# PCB_-_alu40_-_mupusb.net
KiCad netlist of a schematic drawn in EAGLE
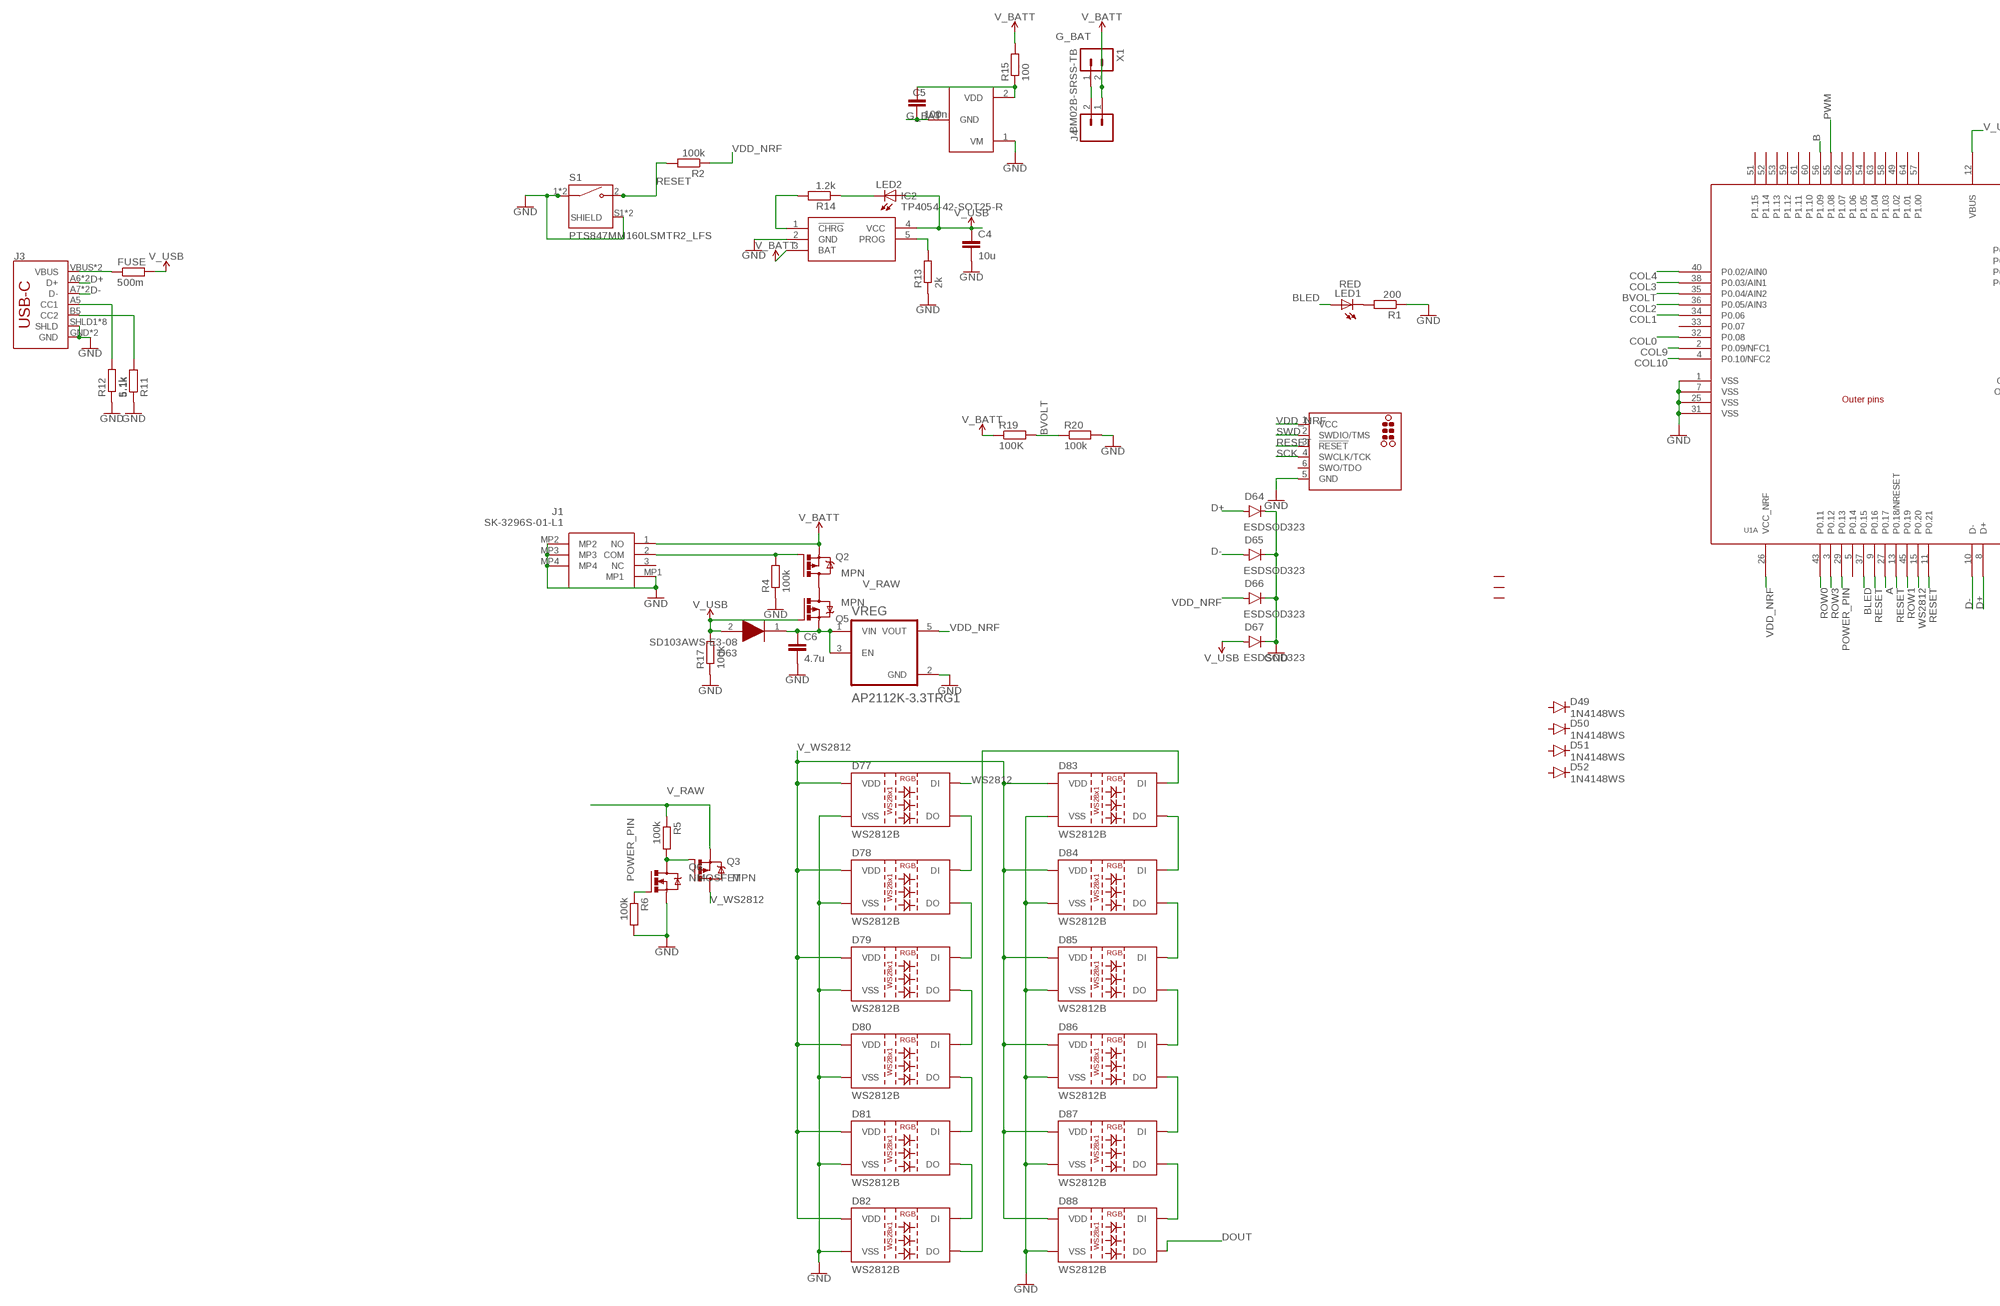
[diagram p0: schematic, sheet 1, part 1 of 2]
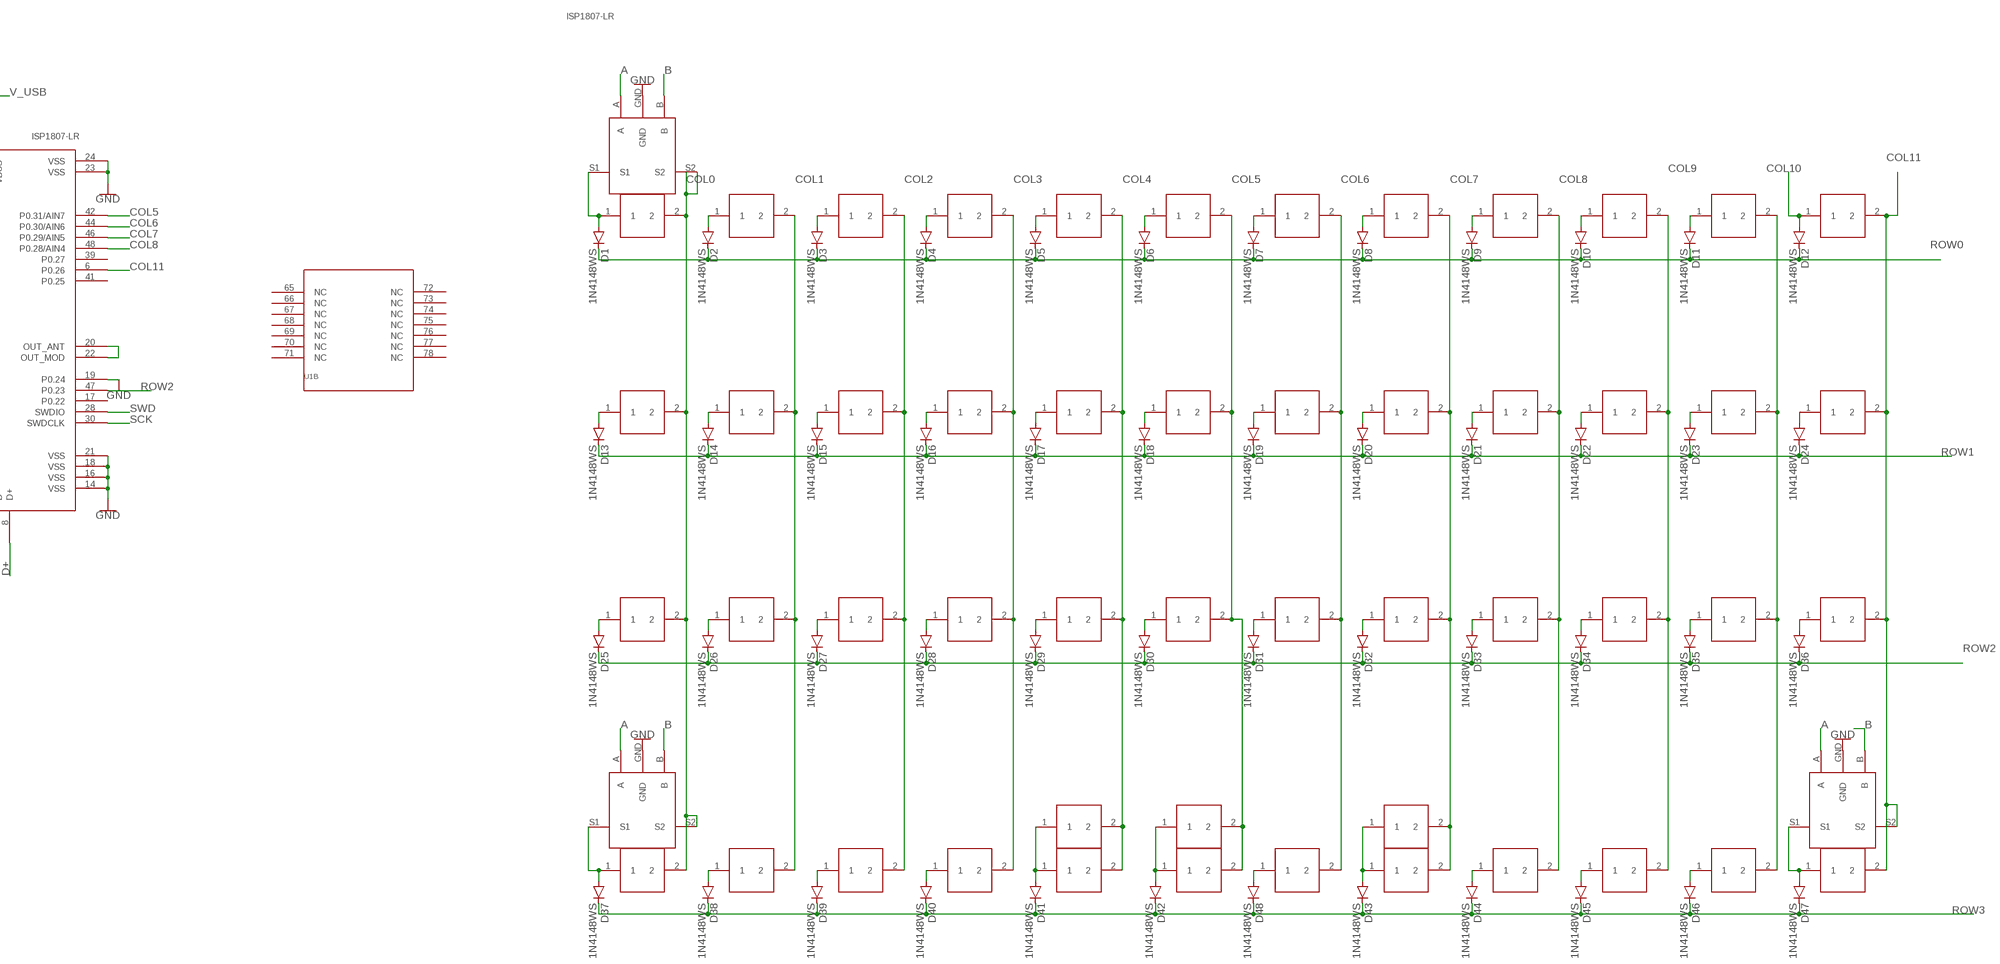
[diagram p1: schematic, sheet 1, part 2 of 2]

(export (version "E")
  (design (tool "Eeschema 10.0.6"))
  (components
    (comp (ref "11")
      (value "CHERRY")
      (footprint "eagle-import:CHERRY")
      (libsource (lib "eagle-import") (part "CHERRY"))
    )
    (comp (ref "11ENC")
      (value "ENCODERHOLE")
      (footprint "eagle-import:ENCODER")
      (libsource (lib "eagle-import") (part "ENCODERHOLE"))
    )
    (comp (ref "12")
      (value "CHERRY")
      (footprint "eagle-import:CHERRY")
      (libsource (lib "eagle-import") (part "CHERRY"))
    )
    (comp (ref "13")
      (value "CHERRY")
      (footprint "eagle-import:CHERRY")
      (libsource (lib "eagle-import") (part "CHERRY"))
    )
    (comp (ref "14")
      (value "CHERRY")
      (footprint "eagle-import:CHERRY")
      (libsource (lib "eagle-import") (part "CHERRY"))
    )
    (comp (ref "15")
      (value "CHERRY")
      (footprint "eagle-import:CHERRY")
      (libsource (lib "eagle-import") (part "CHERRY"))
    )
    (comp (ref "16")
      (value "CHERRY")
      (footprint "eagle-import:CHERRY")
      (libsource (lib "eagle-import") (part "CHERRY"))
    )
    (comp (ref "17")
      (value "CHERRY")
      (footprint "eagle-import:CHERRY")
      (libsource (lib "eagle-import") (part "CHERRY"))
    )
    (comp (ref "18")
      (value "CHERRY")
      (footprint "eagle-import:CHERRY")
      (libsource (lib "eagle-import") (part "CHERRY"))
    )
    (comp (ref "19")
      (value "CHERRY")
      (footprint "eagle-import:CHERRY")
      (libsource (lib "eagle-import") (part "CHERRY"))
    )
    (comp (ref "21")
      (value "CHERRY")
      (footprint "eagle-import:CHERRY")
      (libsource (lib "eagle-import") (part "CHERRY"))
    )
    (comp (ref "22")
      (value "CHERRY")
      (footprint "eagle-import:CHERRY")
      (libsource (lib "eagle-import") (part "CHERRY"))
    )
    (comp (ref "23")
      (value "CHERRY")
      (footprint "eagle-import:CHERRY")
      (libsource (lib "eagle-import") (part "CHERRY"))
    )
    (comp (ref "24")
      (value "CHERRY")
      (footprint "eagle-import:CHERRY")
      (libsource (lib "eagle-import") (part "CHERRY"))
    )
    (comp (ref "25")
      (value "CHERRY")
      (footprint "eagle-import:CHERRY")
      (libsource (lib "eagle-import") (part "CHERRY"))
    )
    (comp (ref "26")
      (value "CHERRY")
      (footprint "eagle-import:CHERRY")
      (libsource (lib "eagle-import") (part "CHERRY"))
    )
    (comp (ref "27")
      (value "CHERRY")
      (footprint "eagle-import:CHERRY")
      (libsource (lib "eagle-import") (part "CHERRY"))
    )
    (comp (ref "28")
      (value "CHERRY")
      (footprint "eagle-import:CHERRY")
      (libsource (lib "eagle-import") (part "CHERRY"))
    )
    (comp (ref "29")
      (value "CHERRY")
      (footprint "eagle-import:CHERRY")
      (libsource (lib "eagle-import") (part "CHERRY"))
    )
    (comp (ref "31")
      (value "CHERRY")
      (footprint "eagle-import:CHERRY")
      (libsource (lib "eagle-import") (part "CHERRY"))
    )
    (comp (ref "32")
      (value "CHERRY")
      (footprint "eagle-import:CHERRY")
      (libsource (lib "eagle-import") (part "CHERRY"))
    )
    (comp (ref "33")
      (value "CHERRY")
      (footprint "eagle-import:CHERRY")
      (libsource (lib "eagle-import") (part "CHERRY"))
    )
    (comp (ref "34")
      (value "CHERRY")
      (footprint "eagle-import:CHERRY")
      (libsource (lib "eagle-import") (part "CHERRY"))
    )
    (comp (ref "35")
      (value "CHERRY")
      (footprint "eagle-import:CHERRY")
      (libsource (lib "eagle-import") (part "CHERRY"))
    )
    (comp (ref "36")
      (value "CHERRY")
      (footprint "eagle-import:CHERRY")
      (libsource (lib "eagle-import") (part "CHERRY"))
    )
    (comp (ref "37")
      (value "CHERRY")
      (footprint "eagle-import:CHERRY")
      (libsource (lib "eagle-import") (part "CHERRY"))
    )
    (comp (ref "38")
      (value "CHERRY")
      (footprint "eagle-import:CHERRY")
      (libsource (lib "eagle-import") (part "CHERRY"))
    )
    (comp (ref "39")
      (value "CHERRY")
      (footprint "eagle-import:CHERRY")
      (libsource (lib "eagle-import") (part "CHERRY"))
    )
    (comp (ref "41")
      (value "CHERRY")
      (footprint "eagle-import:CHERRY")
      (libsource (lib "eagle-import") (part "CHERRY"))
    )
    (comp (ref "41ENC\\")
      (value "ENCODERHOLE")
      (footprint "eagle-import:ENCODER")
      (libsource (lib "eagle-import") (part "ENCODERHOLE"))
    )
    (comp (ref "42")
      (value "CHERRY")
      (footprint "eagle-import:CHERRY")
      (libsource (lib "eagle-import") (part "CHERRY"))
    )
    (comp (ref "43")
      (value "CHERRY")
      (footprint "eagle-import:CHERRY")
      (libsource (lib "eagle-import") (part "CHERRY"))
    )
    (comp (ref "44")
      (value "CHERRY")
      (footprint "eagle-import:CHERRY")
      (libsource (lib "eagle-import") (part "CHERRY"))
    )
    (comp (ref "45")
      (value "CHERRY")
      (footprint "eagle-import:CHERRY")
      (libsource (lib "eagle-import") (part "CHERRY"))
    )
    (comp (ref "45-2")
      (value "CHERRY")
      (footprint "eagle-import:CHERRY")
      (libsource (lib "eagle-import") (part "CHERRY"))
    )
    (comp (ref "46")
      (value "CHERRY")
      (footprint "eagle-import:CHERRY")
      (libsource (lib "eagle-import") (part "CHERRY"))
    )
    (comp (ref "46-2")
      (value "CHERRY")
      (footprint "eagle-import:CHERRY")
      (libsource (lib "eagle-import") (part "CHERRY"))
    )
    (comp (ref "47")
      (value "CHERRY")
      (footprint "eagle-import:CHERRY")
      (libsource (lib "eagle-import") (part "CHERRY"))
    )
    (comp (ref "48")
      (value "CHERRY")
      (footprint "eagle-import:CHERRY")
      (libsource (lib "eagle-import") (part "CHERRY"))
    )
    (comp (ref "48-2")
      (value "CHERRY")
      (footprint "eagle-import:CHERRY")
      (libsource (lib "eagle-import") (part "CHERRY"))
    )
    (comp (ref "49")
      (value "CHERRY")
      (footprint "eagle-import:CHERRY")
      (libsource (lib "eagle-import") (part "CHERRY"))
    )
    (comp (ref "110")
      (value "CHERRY")
      (footprint "eagle-import:CHERRY")
      (libsource (lib "eagle-import") (part "CHERRY"))
    )
    (comp (ref "111")
      (value "CHERRY")
      (footprint "eagle-import:CHERRY")
      (libsource (lib "eagle-import") (part "CHERRY"))
    )
    (comp (ref "112")
      (value "CHERRY")
      (footprint "eagle-import:CHERRY")
      (libsource (lib "eagle-import") (part "CHERRY"))
    )
    (comp (ref "210")
      (value "CHERRY")
      (footprint "eagle-import:CHERRY")
      (libsource (lib "eagle-import") (part "CHERRY"))
    )
    (comp (ref "211")
      (value "CHERRY")
      (footprint "eagle-import:CHERRY")
      (libsource (lib "eagle-import") (part "CHERRY"))
    )
    (comp (ref "212")
      (value "CHERRY")
      (footprint "eagle-import:CHERRY")
      (libsource (lib "eagle-import") (part "CHERRY"))
    )
    (comp (ref "310")
      (value "CHERRY")
      (footprint "eagle-import:CHERRY")
      (libsource (lib "eagle-import") (part "CHERRY"))
    )
    (comp (ref "311")
      (value "CHERRY")
      (footprint "eagle-import:CHERRY")
      (libsource (lib "eagle-import") (part "CHERRY"))
    )
    (comp (ref "312")
      (value "CHERRY")
      (footprint "eagle-import:CHERRY")
      (libsource (lib "eagle-import") (part "CHERRY"))
    )
    (comp (ref "410")
      (value "CHERRY")
      (footprint "eagle-import:CHERRY")
      (libsource (lib "eagle-import") (part "CHERRY"))
    )
    (comp (ref "411")
      (value "CHERRY")
      (footprint "eagle-import:CHERRY")
      (libsource (lib "eagle-import") (part "CHERRY"))
    )
    (comp (ref "412")
      (value "CHERRY")
      (footprint "eagle-import:CHERRY")
      (libsource (lib "eagle-import") (part "CHERRY"))
    )
    (comp (ref "412ENC")
      (value "ENCODERHOLE")
      (footprint "eagle-import:ENCODER")
      (libsource (lib "eagle-import") (part "ENCODERHOLE"))
    )
    (comp (ref "C4")
      (value "10u")
      (footprint "eagle-import:C0603")
      (libsource (lib "eagle-import") (part "resistor_348_C-EUC0603"))
    )
    (comp (ref "C5")
      (value "100n")
      (footprint "eagle-import:C0603")
      (libsource (lib "eagle-import") (part "resistor_348_C-EUC0603"))
    )
    (comp (ref "C6")
      (value "4.7u")
      (footprint "eagle-import:C0603")
      (libsource (lib "eagle-import") (part "C-EUC0603"))
    )
    (comp (ref "D1")
      (value "1N4148WS")
      (footprint "eagle-import:SOD-323")
      (fields
        (field (name "DIGIKEY_PART_NUMBER") "1N4148WSFSTR-ND")
        (field (name "MANUFACTURER") "Diodes Incorporated")
        (field (name "CREATED_BY") "PCBLayout.com")
      )
      (libsource (lib "eagle-import") (part "1N4148WS"))
    )
    (comp (ref "D2")
      (value "1N4148WS")
      (footprint "eagle-import:SOD-323")
      (fields
        (field (name "DIGIKEY_PART_NUMBER") "1N4148WSFSTR-ND")
        (field (name "MANUFACTURER") "Diodes Incorporated")
        (field (name "CREATED_BY") "PCBLayout.com")
      )
      (libsource (lib "eagle-import") (part "1N4148WS"))
    )
    (comp (ref "D3")
      (value "1N4148WS")
      (footprint "eagle-import:SOD-323")
      (fields
        (field (name "DIGIKEY_PART_NUMBER") "1N4148WSFSTR-ND")
        (field (name "MANUFACTURER") "Diodes Incorporated")
        (field (name "CREATED_BY") "PCBLayout.com")
      )
      (libsource (lib "eagle-import") (part "1N4148WS"))
    )
    (comp (ref "D4")
      (value "1N4148WS")
      (footprint "eagle-import:SOD-323")
      (fields
        (field (name "DIGIKEY_PART_NUMBER") "1N4148WSFSTR-ND")
        (field (name "MANUFACTURER") "Diodes Incorporated")
        (field (name "CREATED_BY") "PCBLayout.com")
      )
      (libsource (lib "eagle-import") (part "1N4148WS"))
    )
    (comp (ref "D5")
      (value "1N4148WS")
      (footprint "eagle-import:SOD-323")
      (fields
        (field (name "DIGIKEY_PART_NUMBER") "1N4148WSFSTR-ND")
        (field (name "MANUFACTURER") "Diodes Incorporated")
        (field (name "CREATED_BY") "PCBLayout.com")
      )
      (libsource (lib "eagle-import") (part "1N4148WS"))
    )
    (comp (ref "D6")
      (value "1N4148WS")
      (footprint "eagle-import:SOD-323")
      (fields
        (field (name "DIGIKEY_PART_NUMBER") "1N4148WSFSTR-ND")
        (field (name "MANUFACTURER") "Diodes Incorporated")
        (field (name "CREATED_BY") "PCBLayout.com")
      )
      (libsource (lib "eagle-import") (part "1N4148WS"))
    )
    (comp (ref "D7")
      (value "1N4148WS")
      (footprint "eagle-import:SOD-323")
      (fields
        (field (name "DIGIKEY_PART_NUMBER") "1N4148WSFSTR-ND")
        (field (name "MANUFACTURER") "Diodes Incorporated")
        (field (name "CREATED_BY") "PCBLayout.com")
      )
      (libsource (lib "eagle-import") (part "1N4148WS"))
    )
    (comp (ref "D8")
      (value "1N4148WS")
      (footprint "eagle-import:SOD-323")
      (fields
        (field (name "DIGIKEY_PART_NUMBER") "1N4148WSFSTR-ND")
        (field (name "MANUFACTURER") "Diodes Incorporated")
        (field (name "CREATED_BY") "PCBLayout.com")
      )
      (libsource (lib "eagle-import") (part "1N4148WS"))
    )
    (comp (ref "D9")
      (value "1N4148WS")
      (footprint "eagle-import:SOD-323")
      (fields
        (field (name "DIGIKEY_PART_NUMBER") "1N4148WSFSTR-ND")
        (field (name "MANUFACTURER") "Diodes Incorporated")
        (field (name "CREATED_BY") "PCBLayout.com")
      )
      (libsource (lib "eagle-import") (part "1N4148WS"))
    )
    (comp (ref "D10")
      (value "1N4148WS")
      (footprint "eagle-import:SOD-323")
      (fields
        (field (name "DIGIKEY_PART_NUMBER") "1N4148WSFSTR-ND")
        (field (name "MANUFACTURER") "Diodes Incorporated")
        (field (name "CREATED_BY") "PCBLayout.com")
      )
      (libsource (lib "eagle-import") (part "1N4148WS"))
    )
    (comp (ref "D11")
      (value "1N4148WS")
      (footprint "eagle-import:SOD-323")
      (fields
        (field (name "DIGIKEY_PART_NUMBER") "1N4148WSFSTR-ND")
        (field (name "MANUFACTURER") "Diodes Incorporated")
        (field (name "CREATED_BY") "PCBLayout.com")
      )
      (libsource (lib "eagle-import") (part "1N4148WS"))
    )
    (comp (ref "D12")
      (value "1N4148WS")
      (footprint "eagle-import:SOD-323")
      (fields
        (field (name "DIGIKEY_PART_NUMBER") "1N4148WSFSTR-ND")
        (field (name "MANUFACTURER") "Diodes Incorporated")
        (field (name "CREATED_BY") "PCBLayout.com")
      )
      (libsource (lib "eagle-import") (part "1N4148WS"))
    )
    (comp (ref "D13")
      (value "1N4148WS")
      (footprint "eagle-import:SOD-323")
      (fields
        (field (name "DIGIKEY_PART_NUMBER") "1N4148WSFSTR-ND")
        (field (name "MANUFACTURER") "Diodes Incorporated")
        (field (name "CREATED_BY") "PCBLayout.com")
      )
      (libsource (lib "eagle-import") (part "1N4148WS"))
    )
    (comp (ref "D14")
      (value "1N4148WS")
      (footprint "eagle-import:SOD-323")
      (fields
        (field (name "DIGIKEY_PART_NUMBER") "1N4148WSFSTR-ND")
        (field (name "MANUFACTURER") "Diodes Incorporated")
        (field (name "CREATED_BY") "PCBLayout.com")
      )
      (libsource (lib "eagle-import") (part "1N4148WS"))
    )
    (comp (ref "D15")
      (value "1N4148WS")
      (footprint "eagle-import:SOD-323")
      (fields
        (field (name "DIGIKEY_PART_NUMBER") "1N4148WSFSTR-ND")
        (field (name "MANUFACTURER") "Diodes Incorporated")
        (field (name "CREATED_BY") "PCBLayout.com")
      )
      (libsource (lib "eagle-import") (part "1N4148WS"))
    )
    (comp (ref "D16")
      (value "1N4148WS")
      (footprint "eagle-import:SOD-323")
      (fields
        (field (name "DIGIKEY_PART_NUMBER") "1N4148WSFSTR-ND")
        (field (name "MANUFACTURER") "Diodes Incorporated")
        (field (name "CREATED_BY") "PCBLayout.com")
      )
      (libsource (lib "eagle-import") (part "1N4148WS"))
    )
    (comp (ref "D17")
      (value "1N4148WS")
      (footprint "eagle-import:SOD-323")
      (fields
        (field (name "DIGIKEY_PART_NUMBER") "1N4148WSFSTR-ND")
        (field (name "MANUFACTURER") "Diodes Incorporated")
        (field (name "CREATED_BY") "PCBLayout.com")
      )
      (libsource (lib "eagle-import") (part "1N4148WS"))
    )
    (comp (ref "D18")
      (value "1N4148WS")
      (footprint "eagle-import:SOD-323")
      (fields
        (field (name "DIGIKEY_PART_NUMBER") "1N4148WSFSTR-ND")
        (field (name "MANUFACTURER") "Diodes Incorporated")
        (field (name "CREATED_BY") "PCBLayout.com")
      )
      (libsource (lib "eagle-import") (part "1N4148WS"))
    )
    (comp (ref "D19")
      (value "1N4148WS")
      (footprint "eagle-import:SOD-323")
      (fields
        (field (name "DIGIKEY_PART_NUMBER") "1N4148WSFSTR-ND")
        (field (name "MANUFACTURER") "Diodes Incorporated")
        (field (name "CREATED_BY") "PCBLayout.com")
      )
      (libsource (lib "eagle-import") (part "1N4148WS"))
    )
    (comp (ref "D20")
      (value "1N4148WS")
      (footprint "eagle-import:SOD-323")
      (fields
        (field (name "DIGIKEY_PART_NUMBER") "1N4148WSFSTR-ND")
        (field (name "MANUFACTURER") "Diodes Incorporated")
        (field (name "CREATED_BY") "PCBLayout.com")
      )
      (libsource (lib "eagle-import") (part "1N4148WS"))
    )
    (comp (ref "D21")
      (value "1N4148WS")
      (footprint "eagle-import:SOD-323")
      (fields
        (field (name "DIGIKEY_PART_NUMBER") "1N4148WSFSTR-ND")
        (field (name "MANUFACTURER") "Diodes Incorporated")
        (field (name "CREATED_BY") "PCBLayout.com")
      )
      (libsource (lib "eagle-import") (part "1N4148WS"))
    )
    (comp (ref "D22")
      (value "1N4148WS")
      (footprint "eagle-import:SOD-323")
      (fields
        (field (name "DIGIKEY_PART_NUMBER") "1N4148WSFSTR-ND")
        (field (name "MANUFACTURER") "Diodes Incorporated")
        (field (name "CREATED_BY") "PCBLayout.com")
      )
      (libsource (lib "eagle-import") (part "1N4148WS"))
    )
    (comp (ref "D23")
      (value "1N4148WS")
      (footprint "eagle-import:SOD-323")
      (fields
        (field (name "DIGIKEY_PART_NUMBER") "1N4148WSFSTR-ND")
        (field (name "MANUFACTURER") "Diodes Incorporated")
        (field (name "CREATED_BY") "PCBLayout.com")
      )
      (libsource (lib "eagle-import") (part "1N4148WS"))
    )
    (comp (ref "D24")
      (value "1N4148WS")
      (footprint "eagle-import:SOD-323")
      (fields
        (field (name "DIGIKEY_PART_NUMBER") "1N4148WSFSTR-ND")
        (field (name "MANUFACTURER") "Diodes Incorporated")
        (field (name "CREATED_BY") "PCBLayout.com")
      )
      (libsource (lib "eagle-import") (part "1N4148WS"))
    )
    (comp (ref "D25")
      (value "1N4148WS")
      (footprint "eagle-import:SOD-323")
      (fields
        (field (name "DIGIKEY_PART_NUMBER") "1N4148WSFSTR-ND")
        (field (name "MANUFACTURER") "Diodes Incorporated")
        (field (name "CREATED_BY") "PCBLayout.com")
      )
      (libsource (lib "eagle-import") (part "1N4148WS"))
    )
    (comp (ref "D26")
      (value "1N4148WS")
      (footprint "eagle-import:SOD-323")
      (fields
        (field (name "DIGIKEY_PART_NUMBER") "1N4148WSFSTR-ND")
        (field (name "MANUFACTURER") "Diodes Incorporated")
        (field (name "CREATED_BY") "PCBLayout.com")
      )
      (libsource (lib "eagle-import") (part "1N4148WS"))
    )
    (comp (ref "D27")
      (value "1N4148WS")
      (footprint "eagle-import:SOD-323")
      (fields
        (field (name "DIGIKEY_PART_NUMBER") "1N4148WSFSTR-ND")
        (field (name "MANUFACTURER") "Diodes Incorporated")
        (field (name "CREATED_BY") "PCBLayout.com")
      )
      (libsource (lib "eagle-import") (part "1N4148WS"))
    )
    (comp (ref "D28")
      (value "1N4148WS")
      (footprint "eagle-import:SOD-323")
      (fields
        (field (name "DIGIKEY_PART_NUMBER") "1N4148WSFSTR-ND")
        (field (name "MANUFACTURER") "Diodes Incorporated")
        (field (name "CREATED_BY") "PCBLayout.com")
      )
      (libsource (lib "eagle-import") (part "1N4148WS"))
    )
    (comp (ref "D29")
      (value "1N4148WS")
      (footprint "eagle-import:SOD-323")
      (fields
        (field (name "DIGIKEY_PART_NUMBER") "1N4148WSFSTR-ND")
        (field (name "MANUFACTURER") "Diodes Incorporated")
        (field (name "CREATED_BY") "PCBLayout.com")
      )
      (libsource (lib "eagle-import") (part "1N4148WS"))
    )
    (comp (ref "D30")
      (value "1N4148WS")
      (footprint "eagle-import:SOD-323")
      (fields
        (field (name "DIGIKEY_PART_NUMBER") "1N4148WSFSTR-ND")
        (field (name "MANUFACTURER") "Diodes Incorporated")
        (field (name "CREATED_BY") "PCBLayout.com")
      )
      (libsource (lib "eagle-import") (part "1N4148WS"))
    )
    (comp (ref "D31")
      (value "1N4148WS")
      (footprint "eagle-import:SOD-323")
      (fields
        (field (name "DIGIKEY_PART_NUMBER") "1N4148WSFSTR-ND")
        (field (name "MANUFACTURER") "Diodes Incorporated")
        (field (name "CREATED_BY") "PCBLayout.com")
      )
      (libsource (lib "eagle-import") (part "1N4148WS"))
    )
    (comp (ref "D32")
      (value "1N4148WS")
      (footprint "eagle-import:SOD-323")
      (fields
        (field (name "DIGIKEY_PART_NUMBER") "1N4148WSFSTR-ND")
        (field (name "MANUFACTURER") "Diodes Incorporated")
        (field (name "CREATED_BY") "PCBLayout.com")
      )
      (libsource (lib "eagle-import") (part "1N4148WS"))
    )
    (comp (ref "D33")
      (value "1N4148WS")
      (footprint "eagle-import:SOD-323")
      (fields
        (field (name "DIGIKEY_PART_NUMBER") "1N4148WSFSTR-ND")
        (field (name "MANUFACTURER") "Diodes Incorporated")
        (field (name "CREATED_BY") "PCBLayout.com")
      )
      (libsource (lib "eagle-import") (part "1N4148WS"))
    )
    (comp (ref "D34")
      (value "1N4148WS")
      (footprint "eagle-import:SOD-323")
      (fields
        (field (name "DIGIKEY_PART_NUMBER") "1N4148WSFSTR-ND")
        (field (name "MANUFACTURER") "Diodes Incorporated")
        (field (name "CREATED_BY") "PCBLayout.com")
      )
      (libsource (lib "eagle-import") (part "1N4148WS"))
    )
    (comp (ref "D35")
      (value "1N4148WS")
      (footprint "eagle-import:SOD-323")
      (fields
        (field (name "DIGIKEY_PART_NUMBER") "1N4148WSFSTR-ND")
        (field (name "MANUFACTURER") "Diodes Incorporated")
        (field (name "CREATED_BY") "PCBLayout.com")
      )
      (libsource (lib "eagle-import") (part "1N4148WS"))
    )
    (comp (ref "D36")
      (value "1N4148WS")
      (footprint "eagle-import:SOD-323")
      (fields
        (field (name "DIGIKEY_PART_NUMBER") "1N4148WSFSTR-ND")
        (field (name "MANUFACTURER") "Diodes Incorporated")
        (field (name "CREATED_BY") "PCBLayout.com")
      )
      (libsource (lib "eagle-import") (part "1N4148WS"))
    )
    (comp (ref "D37")
      (value "1N4148WS")
      (footprint "eagle-import:SOD-323")
      (fields
        (field (name "DIGIKEY_PART_NUMBER") "1N4148WSFSTR-ND")
        (field (name "MANUFACTURER") "Diodes Incorporated")
        (field (name "CREATED_BY") "PCBLayout.com")
      )
      (libsource (lib "eagle-import") (part "1N4148WS"))
    )
    (comp (ref "D38")
      (value "1N4148WS")
      (footprint "eagle-import:SOD-323")
      (fields
        (field (name "DIGIKEY_PART_NUMBER") "1N4148WSFSTR-ND")
        (field (name "MANUFACTURER") "Diodes Incorporated")
        (field (name "CREATED_BY") "PCBLayout.com")
      )
      (libsource (lib "eagle-import") (part "1N4148WS"))
    )
    (comp (ref "D39")
      (value "1N4148WS")
      (footprint "eagle-import:SOD-323")
      (fields
        (field (name "DIGIKEY_PART_NUMBER") "1N4148WSFSTR-ND")
        (field (name "MANUFACTURER") "Diodes Incorporated")
        (field (name "CREATED_BY") "PCBLayout.com")
      )
      (libsource (lib "eagle-import") (part "1N4148WS"))
    )
    (comp (ref "D40")
      (value "1N4148WS")
      (footprint "eagle-import:SOD-323")
      (fields
        (field (name "DIGIKEY_PART_NUMBER") "1N4148WSFSTR-ND")
        (field (name "MANUFACTURER") "Diodes Incorporated")
        (field (name "CREATED_BY") "PCBLayout.com")
      )
      (libsource (lib "eagle-import") (part "1N4148WS"))
    )
    (comp (ref "D41")
      (value "1N4148WS")
      (footprint "eagle-import:SOD-323")
      (fields
        (field (name "DIGIKEY_PART_NUMBER") "1N4148WSFSTR-ND")
        (field (name "MANUFACTURER") "Diodes Incorporated")
        (field (name "CREATED_BY") "PCBLayout.com")
      )
      (libsource (lib "eagle-import") (part "1N4148WS"))
    )
    (comp (ref "D42")
      (value "1N4148WS")
      (footprint "eagle-import:SOD-323")
      (fields
        (field (name "DIGIKEY_PART_NUMBER") "1N4148WSFSTR-ND")
        (field (name "MANUFACTURER") "Diodes Incorporated")
        (field (name "CREATED_BY") "PCBLayout.com")
      )
      (libsource (lib "eagle-import") (part "1N4148WS"))
    )
    (comp (ref "D43")
      (value "1N4148WS")
      (footprint "eagle-import:SOD-323")
      (fields
        (field (name "DIGIKEY_PART_NUMBER") "1N4148WSFSTR-ND")
        (field (name "MANUFACTURER") "Diodes Incorporated")
        (field (name "CREATED_BY") "PCBLayout.com")
      )
      (libsource (lib "eagle-import") (part "1N4148WS"))
    )
    (comp (ref "D44")
      (value "1N4148WS")
      (footprint "eagle-import:SOD-323")
      (fields
        (field (name "DIGIKEY_PART_NUMBER") "1N4148WSFSTR-ND")
        (field (name "MANUFACTURER") "Diodes Incorporated")
        (field (name "CREATED_BY") "PCBLayout.com")
      )
      (libsource (lib "eagle-import") (part "1N4148WS"))
    )
    (comp (ref "D45")
      (value "1N4148WS")
      (footprint "eagle-import:SOD-323")
      (fields
        (field (name "DIGIKEY_PART_NUMBER") "1N4148WSFSTR-ND")
        (field (name "MANUFACTURER") "Diodes Incorporated")
        (field (name "CREATED_BY") "PCBLayout.com")
      )
      (libsource (lib "eagle-import") (part "1N4148WS"))
    )
    (comp (ref "D46")
      (value "1N4148WS")
      (footprint "eagle-import:SOD-323")
      (fields
        (field (name "DIGIKEY_PART_NUMBER") "1N4148WSFSTR-ND")
        (field (name "MANUFACTURER") "Diodes Incorporated")
        (field (name "CREATED_BY") "PCBLayout.com")
      )
      (libsource (lib "eagle-import") (part "1N4148WS"))
    )
    (comp (ref "D47")
      (value "1N4148WS")
      (footprint "eagle-import:SOD-323")
      (fields
        (field (name "DIGIKEY_PART_NUMBER") "1N4148WSFSTR-ND")
        (field (name "MANUFACTURER") "Diodes Incorporated")
        (field (name "CREATED_BY") "PCBLayout.com")
      )
      (libsource (lib "eagle-import") (part "1N4148WS"))
    )
    (comp (ref "D48")
      (value "1N4148WS")
      (footprint "eagle-import:SOD-323")
      (fields
        (field (name "DIGIKEY_PART_NUMBER") "1N4148WSFSTR-ND")
        (field (name "MANUFACTURER") "Diodes Incorporated")
        (field (name "CREATED_BY") "PCBLayout.com")
      )
      (libsource (lib "eagle-import") (part "1N4148WS"))
    )
    (comp (ref "D49")
      (value "1N4148WS")
      (footprint "eagle-import:SOD-323")
      (fields
        (field (name "DIGIKEY_PART_NUMBER") "1N4148WSFSTR-ND")
        (field (name "MANUFACTURER") "Diodes Incorporated")
        (field (name "CREATED_BY") "PCBLayout.com")
      )
      (libsource (lib "eagle-import") (part "1N4148WS"))
    )
    (comp (ref "D50")
      (value "1N4148WS")
      (footprint "eagle-import:SOD-323")
      (fields
        (field (name "DIGIKEY_PART_NUMBER") "1N4148WSFSTR-ND")
        (field (name "MANUFACTURER") "Diodes Incorporated")
        (field (name "CREATED_BY") "PCBLayout.com")
      )
      (libsource (lib "eagle-import") (part "1N4148WS"))
    )
    (comp (ref "D51")
      (value "1N4148WS")
      (footprint "eagle-import:SOD-323")
      (fields
        (field (name "DIGIKEY_PART_NUMBER") "1N4148WSFSTR-ND")
        (field (name "MANUFACTURER") "Diodes Incorporated")
        (field (name "CREATED_BY") "PCBLayout.com")
      )
      (libsource (lib "eagle-import") (part "1N4148WS"))
    )
    (comp (ref "D52")
      (value "1N4148WS")
      (footprint "eagle-import:SOD-323")
      (fields
        (field (name "DIGIKEY_PART_NUMBER") "1N4148WSFSTR-ND")
        (field (name "MANUFACTURER") "Diodes Incorporated")
        (field (name "CREATED_BY") "PCBLayout.com")
      )
      (libsource (lib "eagle-import") (part "1N4148WS"))
    )
    (comp (ref "D63")
      (value "SD103AWS-E3-08")
      (footprint "eagle-import:SOD2713X115N")
      (fields (field (name "MOUSER_PART_NUMBER") "78-SD103AWS-E3-08"))
      (libsource (lib "eagle-import") (part "SD103AWS-E3-08"))
    )
    (comp (ref "D64")
      (value "ESDSOD323")
      (footprint "eagle-import:SOD-323")
      (fields (field (name "MANUFACTURER") "Diodes Incorporated") (field (name "CREATED_BY") "PCBLayout.com"))
      (libsource (lib "eagle-import") (part "ESDSOD323"))
    )
    (comp (ref "D65")
      (value "ESDSOD323")
      (footprint "eagle-import:SOD-323")
      (fields (field (name "MANUFACTURER") "Diodes Incorporated") (field (name "CREATED_BY") "PCBLayout.com"))
      (libsource (lib "eagle-import") (part "ESDSOD323"))
    )
    (comp (ref "D66")
      (value "ESDSOD323")
      (footprint "eagle-import:SOD-323")
      (fields (field (name "MANUFACTURER") "Diodes Incorporated") (field (name "CREATED_BY") "PCBLayout.com"))
      (libsource (lib "eagle-import") (part "ESDSOD323"))
    )
    (comp (ref "D67")
      (value "ESDSOD323")
      (footprint "eagle-import:SOD-323")
      (fields (field (name "MANUFACTURER") "Diodes Incorporated") (field (name "CREATED_BY") "PCBLayout.com"))
      (libsource (lib "eagle-import") (part "ESDSOD323"))
    )
    (comp (ref "D77")
      (value "WS2812B")
      (footprint "eagle-import:WS2812B")
      (libsource (lib "eagle-import") (part "WS2812B"))
    )
    (comp (ref "D78")
      (value "WS2812B")
      (footprint "eagle-import:WS2812B")
      (libsource (lib "eagle-import") (part "WS2812B"))
    )
    (comp (ref "D79")
      (value "WS2812B")
      (footprint "eagle-import:WS2812B")
      (libsource (lib "eagle-import") (part "WS2812B"))
    )
    (comp (ref "D80")
      (value "WS2812B")
      (footprint "eagle-import:WS2812B")
      (libsource (lib "eagle-import") (part "WS2812B"))
    )
    (comp (ref "D81")
      (value "WS2812B")
      (footprint "eagle-import:WS2812B")
      (libsource (lib "eagle-import") (part "WS2812B"))
    )
    (comp (ref "D82")
      (value "WS2812B")
      (footprint "eagle-import:WS2812B")
      (libsource (lib "eagle-import") (part "WS2812B"))
    )
    (comp (ref "D83")
      (value "WS2812B")
      (footprint "eagle-import:WS2812B")
      (libsource (lib "eagle-import") (part "WS2812B"))
    )
    (comp (ref "D84")
      (value "WS2812B")
      (footprint "eagle-import:WS2812B")
      (libsource (lib "eagle-import") (part "WS2812B"))
    )
    (comp (ref "D85")
      (value "WS2812B")
      (footprint "eagle-import:WS2812B")
      (libsource (lib "eagle-import") (part "WS2812B"))
    )
    (comp (ref "D86")
      (value "WS2812B")
      (footprint "eagle-import:WS2812B")
      (libsource (lib "eagle-import") (part "WS2812B"))
    )
    (comp (ref "D87")
      (value "WS2812B")
      (footprint "eagle-import:WS2812B")
      (libsource (lib "eagle-import") (part "WS2812B"))
    )
    (comp (ref "D88")
      (value "WS2812B")
      (footprint "eagle-import:WS2812B")
      (libsource (lib "eagle-import") (part "WS2812B"))
    )
    (comp (ref "FUSE")
      (value "500m")
      (footprint "eagle-import:R0603")
      (libsource (lib "eagle-import") (part "rcl_334_R-EU_R0603"))
    )
    (comp (ref "IC1")
      (value "XB3303ASOT23")
      (footprint "eagle-import:SOT23-3")
      (libsource (lib "eagle-import") (part "XB3303ASOT23"))
    )
    (comp (ref "IC2")
      (value "TP4054-42-SOT25-R")
      (footprint "eagle-import:SOT95P280X100-5N")
      (libsource (lib "eagle-import") (part "TP4054-42-SOT25-R"))
    )
    (comp (ref "J1")
      (value "SK-3296S-01-L1")
      (footprint "eagle-import:SK3296S01L1")
      (libsource (lib "eagle-import") (part "SK-3296S-01-L1"))
    )
    (comp (ref "J2")
      (value "TC2030_SWD-MCP-NL")
      (footprint "eagle-import:TC2030-MCP-NL")
      (libsource (lib "eagle-import") (part "TC2030_SWD-MCP-NL"))
    )
    (comp (ref "J3")
      (value "SPARKFUN-CONNECTORS_USB_C")
      (footprint "eagle-import:MUP-MIDMNT-SS")
      (libsource (lib "eagle-import") (part "SPARKFUN-CONNECTORS_USB_C"))
    )
    (comp (ref "J4")
      (value "CONN_02")
      (footprint "eagle-import:1X02")
      (libsource (lib "eagle-import") (part "CONN_02"))
    )
    (comp (ref "LED1")
      (value "RED")
      (footprint "eagle-import:CHIPLED_0805")
      (libsource (lib "eagle-import") (part "LEDCHIPLED_0805"))
    )
    (comp (ref "LED2")
      (value "LEDCHIPLED_0805")
      (footprint "eagle-import:CHIPLED_0805")
      (libsource (lib "eagle-import") (part "LEDCHIPLED_0805"))
    )
    (comp (ref "Q2")
      (value "PMOSFET")
      (footprint "eagle-import:SOT23")
      (fields (field (name "MPN") "SL2301S"))
      (libsource (lib "eagle-import") (part "PMOSFETSOT23_"))
    )
    (comp (ref "Q3")
      (value "PMOSFET")
      (footprint "eagle-import:SOT23")
      (fields (field (name "MPN") "SL2301S"))
      (libsource (lib "eagle-import") (part "PMOSFETSOT23_"))
    )
    (comp (ref "Q5")
      (value "PMOSFET")
      (footprint "eagle-import:SOT23")
      (fields (field (name "MPN") "SL2301S"))
      (libsource (lib "eagle-import") (part "PMOSFETSOT23_"))
    )
    (comp (ref "Q6")
      (value "NMOSFET")
      (footprint "eagle-import:SOT23")
      (libsource (lib "eagle-import") (part "NMOSFETSOT23"))
    )
    (comp (ref "R1")
      (value "200")
      (footprint "eagle-import:R0603")
      (libsource (lib "eagle-import") (part "rcl_334_R-EU_R0603"))
    )
    (comp (ref "R2")
      (value "100k")
      (footprint "eagle-import:R0603")
      (libsource (lib "eagle-import") (part "rcl_334_R-EU_R0603"))
    )
    (comp (ref "R4")
      (value "100k")
      (footprint "eagle-import:R0603")
      (libsource (lib "eagle-import") (part "R-EU_R0603"))
    )
    (comp (ref "R5")
      (value "100k")
      (footprint "eagle-import:R0603")
      (libsource (lib "eagle-import") (part "R-EU_R0603"))
    )
    (comp (ref "R6")
      (value "100k")
      (footprint "eagle-import:R0603")
      (libsource (lib "eagle-import") (part "R-EU_R0603"))
    )
    (comp (ref "R11")
      (value "5.1k")
      (footprint "eagle-import:R0603")
      (libsource (lib "eagle-import") (part "rcl_334_R-EU_R0603"))
    )
    (comp (ref "R12")
      (value "5.1k")
      (footprint "eagle-import:R0603")
      (libsource (lib "eagle-import") (part "rcl_334_R-EU_R0603"))
    )
    (comp (ref "R13")
      (value "2k")
      (footprint "eagle-import:R0603")
      (libsource (lib "eagle-import") (part "rcl_334_R-EU_R0603"))
    )
    (comp (ref "R14")
      (value "1.2k")
      (footprint "eagle-import:R0603")
      (libsource (lib "eagle-import") (part "rcl_334_R-EU_R0603"))
    )
    (comp (ref "R15")
      (value "100")
      (footprint "eagle-import:R0603")
      (libsource (lib "eagle-import") (part "rcl_334_R-EU_R0603"))
    )
    (comp (ref "R17")
      (value "100k")
      (footprint "eagle-import:R0603")
      (libsource (lib "eagle-import") (part "R-EU_R0603"))
    )
    (comp (ref "R19")
      (value "100K")
      (footprint "eagle-import:R0603")
      (libsource (lib "eagle-import") (part "rcl_334_R-EU_R0603"))
    )
    (comp (ref "R20")
      (value "100k")
      (footprint "eagle-import:R0603")
      (libsource (lib "eagle-import") (part "rcl_334_R-EU_R0603"))
    )
    (comp (ref "S1")
      (value "PTS847MM160LSMTR2_LFS")
      (footprint "eagle-import:SW_PTS847MM160LSMTR2_LFS")
      (fields (field (name "MF") "C&K") (field (name "MP") "PTS847MM160LSMTR2 LFS"))
      (libsource (lib "eagle-import") (part "PTS847MM160LSMTR2_LFS"))
    )
    (comp (ref "U$8")
      (value "STAB-2U")
      (footprint "eagle-import:STAB-2U")
      (libsource (lib "eagle-import") (part "STAB-2U"))
    )
    (comp (ref "U$9")
      (value "STAB-2U")
      (footprint "eagle-import:STAB-2U")
      (libsource (lib "eagle-import") (part "STAB-2U"))
    )
    (comp (ref "U$10")
      (value "STAB-2U")
      (footprint "eagle-import:STAB-2U")
      (libsource (lib "eagle-import") (part "STAB-2U"))
    )
    (comp (ref "U1")
      (value "ISP1807-LRISP1807-LR_ISP1807-LR")
      (footprint "eagle-import:ISP1807-LR")
      (fields (field (name "REF") "ISP1807-LR") (field (name "ISP_PART") "ISP1807"))
      (libsource (lib "eagle-import") (part "ISP1807-LRISP1807-LR_ISP1807-LR"))
    )
    (comp (ref "VREG")
      (value "AP2112K-3.3TRG1")
      (footprint "eagle-import:SOT95P285X140-5N")
      (fields (field (name "MF") "Diodes Inc."))
      (libsource (lib "eagle-import") (part "AP2112K-3.3TRG1"))
    )
    (comp (ref "X1")
      (value "BM02B-SRSS-TB")
      (footprint "eagle-import:BM02B-SRSS-TB")
      (libsource (lib "eagle-import") (part "BM02B-SRSS-TB"))
    )
  )
  (nets
    (net (code "1") (name "/A") (class "Default")
      (node (ref "11ENC") (pin "A") (pinfunction "A_A") (pintype "bidirectional"))
      (node (ref "412ENC") (pin "A") (pinfunction "A_A") (pintype "bidirectional"))
      (node (ref "41ENC\\") (pin "A") (pinfunction "A_A") (pintype "bidirectional"))
      (node (ref "U1") (pin "27") (pinfunction "P0.17_27") (pintype "bidirectional"))
    )
    (net (code "2") (name "/B") (class "Default")
      (node (ref "11ENC") (pin "B") (pinfunction "B_B") (pintype "bidirectional"))
      (node (ref "412ENC") (pin "B") (pinfunction "B_B") (pintype "bidirectional"))
      (node (ref "41ENC\\") (pin "B") (pinfunction "B_B") (pintype "bidirectional"))
      (node (ref "U1") (pin "56") (pinfunction "P1.09_56") (pintype "bidirectional"))
    )
    (net (code "3") (name "/BLED") (class "Default")
      (node (ref "LED1") (pin "A") (pinfunction "A_A") (pintype "passive"))
      (node (ref "U1") (pin "37") (pinfunction "P0.15_37") (pintype "bidirectional"))
    )
    (net (code "4") (name "/BVOLT") (class "Default")
      (node (ref "R19") (pin "2") (pinfunction "2_2") (pintype "passive"))
      (node (ref "R20") (pin "1") (pinfunction "1_1") (pintype "passive"))
      (node (ref "U1") (pin "35") (pinfunction "P0.04/AIN2_35") (pintype "bidirectional"))
    )
    (net (code "5") (name "/COL0") (class "Default")
      (node (ref "11") (pin "2") (pinfunction "2_2") (pintype "bidirectional"))
      (node (ref "11ENC") (pin "S2") (pinfunction "S2_S2") (pintype "bidirectional"))
      (node (ref "21") (pin "2") (pinfunction "2_2") (pintype "bidirectional"))
      (node (ref "31") (pin "2") (pinfunction "2_2") (pintype "bidirectional"))
      (node (ref "41") (pin "2") (pinfunction "2_2") (pintype "bidirectional"))
      (node (ref "41ENC\\") (pin "S2") (pinfunction "S2_S2") (pintype "bidirectional"))
      (node (ref "U1") (pin "32") (pinfunction "P0.08_32") (pintype "bidirectional"))
    )
    (net (code "6") (name "/COL1") (class "Default")
      (node (ref "12") (pin "2") (pinfunction "2_2") (pintype "bidirectional"))
      (node (ref "22") (pin "2") (pinfunction "2_2") (pintype "bidirectional"))
      (node (ref "32") (pin "2") (pinfunction "2_2") (pintype "bidirectional"))
      (node (ref "42") (pin "2") (pinfunction "2_2") (pintype "bidirectional"))
      (node (ref "U1") (pin "34") (pinfunction "P0.06_34") (pintype "bidirectional"))
    )
    (net (code "7") (name "/COL2") (class "Default")
      (node (ref "13") (pin "2") (pinfunction "2_2") (pintype "bidirectional"))
      (node (ref "23") (pin "2") (pinfunction "2_2") (pintype "bidirectional"))
      (node (ref "33") (pin "2") (pinfunction "2_2") (pintype "bidirectional"))
      (node (ref "43") (pin "2") (pinfunction "2_2") (pintype "bidirectional"))
      (node (ref "U1") (pin "36") (pinfunction "P0.05/AIN3_36") (pintype "bidirectional"))
    )
    (net (code "8") (name "/COL3") (class "Default")
      (node (ref "14") (pin "2") (pinfunction "2_2") (pintype "bidirectional"))
      (node (ref "24") (pin "2") (pinfunction "2_2") (pintype "bidirectional"))
      (node (ref "34") (pin "2") (pinfunction "2_2") (pintype "bidirectional"))
      (node (ref "44") (pin "2") (pinfunction "2_2") (pintype "bidirectional"))
      (node (ref "U1") (pin "38") (pinfunction "P0.03/AIN1_38") (pintype "bidirectional"))
    )
    (net (code "9") (name "/COL4") (class "Default")
      (node (ref "15") (pin "2") (pinfunction "2_2") (pintype "bidirectional"))
      (node (ref "25") (pin "2") (pinfunction "2_2") (pintype "bidirectional"))
      (node (ref "35") (pin "2") (pinfunction "2_2") (pintype "bidirectional"))
      (node (ref "45") (pin "2") (pinfunction "2_2") (pintype "bidirectional"))
      (node (ref "45-2") (pin "2") (pinfunction "2_2") (pintype "bidirectional"))
      (node (ref "U1") (pin "40") (pinfunction "P0.02/AIN0_40") (pintype "bidirectional"))
    )
    (net (code "10") (name "/COL5") (class "Default")
      (node (ref "16") (pin "2") (pinfunction "2_2") (pintype "bidirectional"))
      (node (ref "26") (pin "2") (pinfunction "2_2") (pintype "bidirectional"))
      (node (ref "36") (pin "2") (pinfunction "2_2") (pintype "bidirectional"))
      (node (ref "46") (pin "2") (pinfunction "2_2") (pintype "bidirectional"))
      (node (ref "46-2") (pin "2") (pinfunction "2_2") (pintype "bidirectional"))
      (node (ref "U1") (pin "42") (pinfunction "P0.31/AIN7_42") (pintype "bidirectional"))
    )
    (net (code "11") (name "/COL6") (class "Default")
      (node (ref "17") (pin "2") (pinfunction "2_2") (pintype "bidirectional"))
      (node (ref "27") (pin "2") (pinfunction "2_2") (pintype "bidirectional"))
      (node (ref "37") (pin "2") (pinfunction "2_2") (pintype "bidirectional"))
      (node (ref "47") (pin "2") (pinfunction "2_2") (pintype "bidirectional"))
      (node (ref "U1") (pin "44") (pinfunction "P0.30/AIN6_44") (pintype "bidirectional"))
    )
    (net (code "12") (name "/COL7") (class "Default")
      (node (ref "18") (pin "2") (pinfunction "2_2") (pintype "bidirectional"))
      (node (ref "28") (pin "2") (pinfunction "2_2") (pintype "bidirectional"))
      (node (ref "38") (pin "2") (pinfunction "2_2") (pintype "bidirectional"))
      (node (ref "48") (pin "2") (pinfunction "2_2") (pintype "bidirectional"))
      (node (ref "48-2") (pin "2") (pinfunction "2_2") (pintype "bidirectional"))
      (node (ref "U1") (pin "46") (pinfunction "P0.29/AIN5_46") (pintype "bidirectional"))
    )
    (net (code "13") (name "/COL8") (class "Default")
      (node (ref "19") (pin "2") (pinfunction "2_2") (pintype "bidirectional"))
      (node (ref "29") (pin "2") (pinfunction "2_2") (pintype "bidirectional"))
      (node (ref "39") (pin "2") (pinfunction "2_2") (pintype "bidirectional"))
      (node (ref "49") (pin "2") (pinfunction "2_2") (pintype "bidirectional"))
      (node (ref "U1") (pin "48") (pinfunction "P0.28/AIN4_48") (pintype "bidirectional"))
    )
    (net (code "14") (name "/COL9") (class "Default")
      (node (ref "110") (pin "2") (pinfunction "2_2") (pintype "bidirectional"))
      (node (ref "210") (pin "2") (pinfunction "2_2") (pintype "bidirectional"))
      (node (ref "310") (pin "2") (pinfunction "2_2") (pintype "bidirectional"))
      (node (ref "410") (pin "2") (pinfunction "2_2") (pintype "bidirectional"))
      (node (ref "U1") (pin "2") (pinfunction "P0.09/NFC1_2") (pintype "bidirectional"))
    )
    (net (code "15") (name "/COL10") (class "Default")
      (node (ref "111") (pin "2") (pinfunction "2_2") (pintype "bidirectional"))
      (node (ref "211") (pin "2") (pinfunction "2_2") (pintype "bidirectional"))
      (node (ref "311") (pin "2") (pinfunction "2_2") (pintype "bidirectional"))
      (node (ref "411") (pin "2") (pinfunction "2_2") (pintype "bidirectional"))
      (node (ref "U1") (pin "4") (pinfunction "P0.10/NFC2_4") (pintype "bidirectional"))
    )
    (net (code "16") (name "/COL11") (class "Default")
      (node (ref "112") (pin "2") (pinfunction "2_2") (pintype "bidirectional"))
      (node (ref "212") (pin "2") (pinfunction "2_2") (pintype "bidirectional"))
      (node (ref "312") (pin "2") (pinfunction "2_2") (pintype "bidirectional"))
      (node (ref "412") (pin "2") (pinfunction "2_2") (pintype "bidirectional"))
      (node (ref "412ENC") (pin "S2") (pinfunction "S2_S2") (pintype "bidirectional"))
      (node (ref "U1") (pin "6") (pinfunction "P0.26_6") (pintype "bidirectional"))
    )
    (net (code "17") (name "/D+") (class "Default")
      (node (ref "D64") (pin "A") (pinfunction "A_A") (pintype "passive"))
      (node (ref "J3") (pin "A6") (pinfunction "D+_A6") (pintype "bidirectional"))
      (node (ref "J3") (pin "B6") (pinfunction "D+_B6") (pintype "bidirectional"))
      (node (ref "U1") (pin "8") (pinfunction "D+_8") (pintype "power_in"))
    )
    (net (code "18") (name "/D-") (class "Default")
      (node (ref "D65") (pin "A") (pinfunction "A_A") (pintype "passive"))
      (node (ref "J3") (pin "A7") (pinfunction "D-_A7") (pintype "bidirectional"))
      (node (ref "J3") (pin "B7") (pinfunction "D-_B7") (pintype "bidirectional"))
      (node (ref "U1") (pin "10") (pinfunction "D-_10") (pintype "power_in"))
    )
    (net (code "19") (name "/DOUT") (class "Default")
      (node (ref "D88") (pin "2") (pinfunction "DO_2") (pintype "bidirectional"))
    )
    (net (code "20") (name "/G_BAT") (class "Default")
      (node (ref "C5") (pin "2") (pinfunction "2_2") (pintype "passive"))
      (node (ref "IC1") (pin "3") (pinfunction "GND_3") (pintype "bidirectional"))
      (node (ref "J4") (pin "2") (pinfunction "2_2") (pintype "passive"))
      (node (ref "X1") (pin "1") (pinfunction "1_1") (pintype "passive"))
    )
    (net (code "21") (name "/POWER_PIN") (class "Default")
      (node (ref "Q6") (pin "1") (pinfunction "G_1") (pintype "passive"))
      (node (ref "R6") (pin "1") (pinfunction "1_1") (pintype "passive"))
      (node (ref "U1") (pin "29") (pinfunction "P0.13_29") (pintype "bidirectional"))
    )
    (net (code "22") (name "/PWM") (class "Default")
      (node (ref "U1") (pin "55") (pinfunction "P1.08_55") (pintype "bidirectional"))
    )
    (net (code "23") (name "/RESET") (class "Default")
      (node (ref "J2") (pin "3") (pinfunction "~{RESET}_3") (pintype "output"))
      (node (ref "R2") (pin "2") (pinfunction "2_2") (pintype "passive"))
      (node (ref "S1") (pin "2") (pinfunction "NO_2") (pintype "passive"))
      (node (ref "U1") (pin "11") (pinfunction "P0.21_11") (pintype "bidirectional"))
      (node (ref "U1") (pin "13") (pinfunction "P0.18/NRESET_13") (pintype "bidirectional"))
      (node (ref "U1") (pin "9") (pinfunction "P0.16_9") (pintype "bidirectional"))
    )
    (net (code "24") (name "/ROW0") (class "Default")
      (node (ref "D1") (pin "C") (pinfunction "C_C") (pintype "passive"))
      (node (ref "D10") (pin "C") (pinfunction "C_C") (pintype "passive"))
      (node (ref "D11") (pin "C") (pinfunction "C_C") (pintype "passive"))
      (node (ref "D12") (pin "C") (pinfunction "C_C") (pintype "passive"))
      (node (ref "D2") (pin "C") (pinfunction "C_C") (pintype "passive"))
      (node (ref "D3") (pin "C") (pinfunction "C_C") (pintype "passive"))
      (node (ref "D4") (pin "C") (pinfunction "C_C") (pintype "passive"))
      (node (ref "D5") (pin "C") (pinfunction "C_C") (pintype "passive"))
      (node (ref "D6") (pin "C") (pinfunction "C_C") (pintype "passive"))
      (node (ref "D7") (pin "C") (pinfunction "C_C") (pintype "passive"))
      (node (ref "D8") (pin "C") (pinfunction "C_C") (pintype "passive"))
      (node (ref "D9") (pin "C") (pinfunction "C_C") (pintype "passive"))
      (node (ref "U1") (pin "43") (pinfunction "P0.11_43") (pintype "bidirectional"))
    )
    (net (code "25") (name "/ROW1") (class "Default")
      (node (ref "D13") (pin "C") (pinfunction "C_C") (pintype "passive"))
      (node (ref "D14") (pin "C") (pinfunction "C_C") (pintype "passive"))
      (node (ref "D15") (pin "C") (pinfunction "C_C") (pintype "passive"))
      (node (ref "D16") (pin "C") (pinfunction "C_C") (pintype "passive"))
      (node (ref "D17") (pin "C") (pinfunction "C_C") (pintype "passive"))
      (node (ref "D18") (pin "C") (pinfunction "C_C") (pintype "passive"))
      (node (ref "D19") (pin "C") (pinfunction "C_C") (pintype "passive"))
      (node (ref "D20") (pin "C") (pinfunction "C_C") (pintype "passive"))
      (node (ref "D21") (pin "C") (pinfunction "C_C") (pintype "passive"))
      (node (ref "D22") (pin "C") (pinfunction "C_C") (pintype "passive"))
      (node (ref "D23") (pin "C") (pinfunction "C_C") (pintype "passive"))
      (node (ref "D24") (pin "C") (pinfunction "C_C") (pintype "passive"))
      (node (ref "U1") (pin "45") (pinfunction "P0.19_45") (pintype "bidirectional"))
    )
    (net (code "26") (name "/ROW2") (class "Default")
      (node (ref "D25") (pin "C") (pinfunction "C_C") (pintype "passive"))
      (node (ref "D26") (pin "C") (pinfunction "C_C") (pintype "passive"))
      (node (ref "D27") (pin "C") (pinfunction "C_C") (pintype "passive"))
      (node (ref "D28") (pin "C") (pinfunction "C_C") (pintype "passive"))
      (node (ref "D29") (pin "C") (pinfunction "C_C") (pintype "passive"))
      (node (ref "D30") (pin "C") (pinfunction "C_C") (pintype "passive"))
      (node (ref "D31") (pin "C") (pinfunction "C_C") (pintype "passive"))
      (node (ref "D32") (pin "C") (pinfunction "C_C") (pintype "passive"))
      (node (ref "D33") (pin "C") (pinfunction "C_C") (pintype "passive"))
      (node (ref "D34") (pin "C") (pinfunction "C_C") (pintype "passive"))
      (node (ref "D35") (pin "C") (pinfunction "C_C") (pintype "passive"))
      (node (ref "D36") (pin "C") (pinfunction "C_C") (pintype "passive"))
      (node (ref "U1") (pin "47") (pinfunction "P0.23_47") (pintype "bidirectional"))
    )
    (net (code "27") (name "/ROW3") (class "Default")
      (node (ref "D37") (pin "C") (pinfunction "C_C") (pintype "passive"))
      (node (ref "D38") (pin "C") (pinfunction "C_C") (pintype "passive"))
      (node (ref "D39") (pin "C") (pinfunction "C_C") (pintype "passive"))
      (node (ref "D40") (pin "C") (pinfunction "C_C") (pintype "passive"))
      (node (ref "D41") (pin "C") (pinfunction "C_C") (pintype "passive"))
      (node (ref "D42") (pin "C") (pinfunction "C_C") (pintype "passive"))
      (node (ref "D43") (pin "C") (pinfunction "C_C") (pintype "passive"))
      (node (ref "D44") (pin "C") (pinfunction "C_C") (pintype "passive"))
      (node (ref "D45") (pin "C") (pinfunction "C_C") (pintype "passive"))
      (node (ref "D46") (pin "C") (pinfunction "C_C") (pintype "passive"))
      (node (ref "D47") (pin "C") (pinfunction "C_C") (pintype "passive"))
      (node (ref "D48") (pin "C") (pinfunction "C_C") (pintype "passive"))
      (node (ref "U1") (pin "3") (pinfunction "P0.12_3") (pintype "bidirectional"))
    )
    (net (code "28") (name "/SCK") (class "Default")
      (node (ref "J2") (pin "4") (pinfunction "SWCLK/TCK_4") (pintype "output"))
      (node (ref "U1") (pin "30") (pinfunction "SWDCLK_30") (pintype "input"))
    )
    (net (code "29") (name "/SWD") (class "Default")
      (node (ref "J2") (pin "2") (pinfunction "SWDIO/TMS_2") (pintype "bidirectional"))
      (node (ref "U1") (pin "28") (pinfunction "SWDIO_28") (pintype "bidirectional"))
    )
    (net (code "30") (name "/VDD_NRF") (class "Default")
      (node (ref "D66") (pin "A") (pinfunction "A_A") (pintype "passive"))
      (node (ref "J2") (pin "1") (pinfunction "VCC_1") (pintype "passive"))
      (node (ref "R2") (pin "1") (pinfunction "1_1") (pintype "passive"))
      (node (ref "U1") (pin "26") (pinfunction "VCC_NRF_26") (pintype "power_in"))
      (node (ref "VREG") (pin "5") (pinfunction "VOUT_5") (pintype "power_in"))
    )
    (net (code "31") (name "/V_RAW") (class "Default")
      (node (ref "C6") (pin "1") (pinfunction "1_1") (pintype "passive"))
      (node (ref "D63") (pin "1") (pinfunction "K_1") (pintype "bidirectional"))
      (node (ref "Q3") (pin "2") (pinfunction "S_2") (pintype "passive"))
      (node (ref "Q5") (pin "2") (pinfunction "S_2") (pintype "passive"))
      (node (ref "R5") (pin "1") (pinfunction "1_1") (pintype "passive"))
      (node (ref "VREG") (pin "1") (pinfunction "VIN_1") (pintype "power_in"))
      (node (ref "VREG") (pin "3") (pinfunction "EN_3") (pintype "input"))
    )
    (net (code "32") (name "/V_WS2812") (class "Default")
      (node (ref "D77") (pin "1") (pinfunction "VDD_1") (pintype "bidirectional"))
      (node (ref "D78") (pin "1") (pinfunction "VDD_1") (pintype "bidirectional"))
      (node (ref "D79") (pin "1") (pinfunction "VDD_1") (pintype "bidirectional"))
      (node (ref "D80") (pin "1") (pinfunction "VDD_1") (pintype "bidirectional"))
      (node (ref "D81") (pin "1") (pinfunction "VDD_1") (pintype "bidirectional"))
      (node (ref "D82") (pin "1") (pinfunction "VDD_1") (pintype "bidirectional"))
      (node (ref "D83") (pin "1") (pinfunction "VDD_1") (pintype "bidirectional"))
      (node (ref "D84") (pin "1") (pinfunction "VDD_1") (pintype "bidirectional"))
      (node (ref "D85") (pin "1") (pinfunction "VDD_1") (pintype "bidirectional"))
      (node (ref "D86") (pin "1") (pinfunction "VDD_1") (pintype "bidirectional"))
      (node (ref "D87") (pin "1") (pinfunction "VDD_1") (pintype "bidirectional"))
      (node (ref "D88") (pin "1") (pinfunction "VDD_1") (pintype "bidirectional"))
      (node (ref "Q3") (pin "3") (pinfunction "D_3") (pintype "passive"))
    )
    (net (code "33") (name "/WS2812") (class "Default")
      (node (ref "D77") (pin "4") (pinfunction "DI_4") (pintype "bidirectional"))
      (node (ref "U1") (pin "15") (pinfunction "P0.20_15") (pintype "bidirectional"))
    )
    (net (code "34") (name "GND") (class "Default")
      (node (ref "11ENC") (pin "GND") (pinfunction "GND_GND") (pintype "bidirectional"))
      (node (ref "412ENC") (pin "GND") (pinfunction "GND_GND") (pintype "bidirectional"))
      (node (ref "41ENC\\") (pin "GND") (pinfunction "GND_GND") (pintype "bidirectional"))
      (node (ref "C4") (pin "2") (pinfunction "2_2") (pintype "passive"))
      (node (ref "C6") (pin "2") (pinfunction "2_2") (pintype "passive"))
      (node (ref "D64") (pin "C") (pinfunction "C_C") (pintype "passive"))
      (node (ref "D65") (pin "C") (pinfunction "C_C") (pintype "passive"))
      (node (ref "D66") (pin "C") (pinfunction "C_C") (pintype "passive"))
      (node (ref "D67") (pin "C") (pinfunction "C_C") (pintype "passive"))
      (node (ref "D77") (pin "3") (pinfunction "VSS_3") (pintype "bidirectional"))
      (node (ref "D78") (pin "3") (pinfunction "VSS_3") (pintype "bidirectional"))
      (node (ref "D79") (pin "3") (pinfunction "VSS_3") (pintype "bidirectional"))
      (node (ref "D80") (pin "3") (pinfunction "VSS_3") (pintype "bidirectional"))
      (node (ref "D81") (pin "3") (pinfunction "VSS_3") (pintype "bidirectional"))
      (node (ref "D82") (pin "3") (pinfunction "VSS_3") (pintype "bidirectional"))
      (node (ref "D83") (pin "3") (pinfunction "VSS_3") (pintype "bidirectional"))
      (node (ref "D84") (pin "3") (pinfunction "VSS_3") (pintype "bidirectional"))
      (node (ref "D85") (pin "3") (pinfunction "VSS_3") (pintype "bidirectional"))
      (node (ref "D86") (pin "3") (pinfunction "VSS_3") (pintype "bidirectional"))
      (node (ref "D87") (pin "3") (pinfunction "VSS_3") (pintype "bidirectional"))
      (node (ref "D88") (pin "3") (pinfunction "VSS_3") (pintype "bidirectional"))
      (node (ref "IC1") (pin "1") (pinfunction "VM_1") (pintype "bidirectional"))
      (node (ref "IC2") (pin "2") (pinfunction "GND_2") (pintype "bidirectional"))
      (node (ref "J1") (pin "MP1") (pinfunction "MP1_MP1") (pintype "bidirectional"))
      (node (ref "J1") (pin "MP2") (pinfunction "MP2_MP2") (pintype "bidirectional"))
      (node (ref "J1") (pin "MP3") (pinfunction "MP3_MP3") (pintype "bidirectional"))
      (node (ref "J1") (pin "MP4") (pinfunction "MP4_MP4") (pintype "bidirectional"))
      (node (ref "J2") (pin "5") (pinfunction "GND_5") (pintype "passive"))
      (node (ref "J3") (pin "GND") (pinfunction "GND_GND") (pintype "bidirectional"))
      (node (ref "J3") (pin "GND2") (pinfunction "GND_GND2") (pintype "bidirectional"))
      (node (ref "J3") (pin "SHLD1") (pinfunction "SHLD_SHLD1") (pintype "bidirectional"))
      (node (ref "J3") (pin "SHLD2") (pinfunction "SHLD_SHLD2") (pintype "bidirectional"))
      (node (ref "J3") (pin "SHLD3") (pinfunction "SHLD_SHLD3") (pintype "bidirectional"))
      (node (ref "J3") (pin "SHLD4") (pinfunction "SHLD_SHLD4") (pintype "bidirectional"))
      (node (ref "J3") (pin "SHLD5") (pinfunction "SHLD_SHLD5") (pintype "bidirectional"))
      (node (ref "J3") (pin "SHLD6") (pinfunction "SHLD_SHLD6") (pintype "bidirectional"))
      (node (ref "J3") (pin "SHLD7") (pinfunction "SHLD_SHLD7") (pintype "bidirectional"))
      (node (ref "J3") (pin "SHLD8") (pinfunction "SHLD_SHLD8") (pintype "bidirectional"))
      (node (ref "Q6") (pin "2") (pinfunction "S_2") (pintype "passive"))
      (node (ref "R1") (pin "1") (pinfunction "1_1") (pintype "passive"))
      (node (ref "R11") (pin "1") (pinfunction "1_1") (pintype "passive"))
      (node (ref "R12") (pin "1") (pinfunction "1_1") (pintype "passive"))
      (node (ref "R13") (pin "1") (pinfunction "1_1") (pintype "passive"))
      (node (ref "R17") (pin "1") (pinfunction "1_1") (pintype "passive"))
      (node (ref "R20") (pin "2") (pinfunction "2_2") (pintype "passive"))
      (node (ref "R4") (pin "1") (pinfunction "1_1") (pintype "passive"))
      (node (ref "R6") (pin "2") (pinfunction "2_2") (pintype "passive"))
      (node (ref "S1") (pin "1") (pinfunction "COM_1") (pintype "passive"))
      (node (ref "S1") (pin "3") (pinfunction "COM_3") (pintype "passive"))
      (node (ref "S1") (pin "S1") (pinfunction "SHIELD_S1") (pintype "passive"))
      (node (ref "S1") (pin "S2") (pinfunction "SHIELD_S2") (pintype "passive"))
      (node (ref "U1") (pin "1") (pinfunction "VSS_1") (pintype "power_in"))
      (node (ref "U1") (pin "14") (pinfunction "VSS_14") (pintype "power_in"))
      (node (ref "U1") (pin "16") (pinfunction "VSS_16") (pintype "power_in"))
      (node (ref "U1") (pin "18") (pinfunction "VSS_18") (pintype "power_in"))
      (node (ref "U1") (pin "19") (pinfunction "P0.24_19") (pintype "bidirectional"))
      (node (ref "U1") (pin "21") (pinfunction "VSS_21") (pintype "power_in"))
      (node (ref "U1") (pin "23") (pinfunction "VSS_23") (pintype "power_in"))
      (node (ref "U1") (pin "24") (pinfunction "VSS_24") (pintype "power_in"))
      (node (ref "U1") (pin "25") (pinfunction "VSS_25") (pintype "power_in"))
      (node (ref "U1") (pin "31") (pinfunction "VSS_31") (pintype "power_in"))
      (node (ref "U1") (pin "7") (pinfunction "VSS_7") (pintype "power_in"))
      (node (ref "VREG") (pin "2") (pinfunction "GND_2") (pintype "power_in"))
    )
    (net (code "35") (name "Net-(11-Pad1)") (class "Default")
      (node (ref "11") (pin "1") (pinfunction "1_1") (pintype "bidirectional"))
      (node (ref "11ENC") (pin "S1") (pinfunction "S1_S1") (pintype "bidirectional"))
      (node (ref "D1") (pin "A") (pinfunction "A_A") (pintype "passive"))
    )
    (net (code "36") (name "Net-(12-Pad1)") (class "Default")
      (node (ref "12") (pin "1") (pinfunction "1_1") (pintype "bidirectional"))
      (node (ref "D2") (pin "A") (pinfunction "A_A") (pintype "passive"))
    )
    (net (code "37") (name "Net-(13-Pad1)") (class "Default")
      (node (ref "13") (pin "1") (pinfunction "1_1") (pintype "bidirectional"))
      (node (ref "D3") (pin "A") (pinfunction "A_A") (pintype "passive"))
    )
    (net (code "38") (name "Net-(14-Pad1)") (class "Default")
      (node (ref "14") (pin "1") (pinfunction "1_1") (pintype "bidirectional"))
      (node (ref "D4") (pin "A") (pinfunction "A_A") (pintype "passive"))
    )
    (net (code "39") (name "Net-(15-Pad1)") (class "Default")
      (node (ref "15") (pin "1") (pinfunction "1_1") (pintype "bidirectional"))
      (node (ref "D5") (pin "A") (pinfunction "A_A") (pintype "passive"))
    )
    (net (code "40") (name "Net-(16-Pad1)") (class "Default")
      (node (ref "16") (pin "1") (pinfunction "1_1") (pintype "bidirectional"))
      (node (ref "D6") (pin "A") (pinfunction "A_A") (pintype "passive"))
    )
    (net (code "41") (name "Net-(17-Pad1)") (class "Default")
      (node (ref "17") (pin "1") (pinfunction "1_1") (pintype "bidirectional"))
      (node (ref "D7") (pin "A") (pinfunction "A_A") (pintype "passive"))
    )
    (net (code "42") (name "Net-(18-Pad1)") (class "Default")
      (node (ref "18") (pin "1") (pinfunction "1_1") (pintype "bidirectional"))
      (node (ref "D8") (pin "A") (pinfunction "A_A") (pintype "passive"))
    )
    (net (code "43") (name "Net-(19-Pad1)") (class "Default")
      (node (ref "19") (pin "1") (pinfunction "1_1") (pintype "bidirectional"))
      (node (ref "D9") (pin "A") (pinfunction "A_A") (pintype "passive"))
    )
    (net (code "44") (name "Net-(21-Pad1)") (class "Default")
      (node (ref "21") (pin "1") (pinfunction "1_1") (pintype "bidirectional"))
      (node (ref "D13") (pin "A") (pinfunction "A_A") (pintype "passive"))
    )
    (net (code "45") (name "Net-(22-Pad1)") (class "Default")
      (node (ref "22") (pin "1") (pinfunction "1_1") (pintype "bidirectional"))
      (node (ref "D14") (pin "A") (pinfunction "A_A") (pintype "passive"))
    )
    (net (code "46") (name "Net-(23-Pad1)") (class "Default")
      (node (ref "23") (pin "1") (pinfunction "1_1") (pintype "bidirectional"))
      (node (ref "D15") (pin "A") (pinfunction "A_A") (pintype "passive"))
    )
    (net (code "47") (name "Net-(24-Pad1)") (class "Default")
      (node (ref "24") (pin "1") (pinfunction "1_1") (pintype "bidirectional"))
      (node (ref "D16") (pin "A") (pinfunction "A_A") (pintype "passive"))
    )
    (net (code "48") (name "Net-(25-Pad1)") (class "Default")
      (node (ref "25") (pin "1") (pinfunction "1_1") (pintype "bidirectional"))
      (node (ref "D17") (pin "A") (pinfunction "A_A") (pintype "passive"))
    )
    (net (code "49") (name "Net-(26-Pad1)") (class "Default")
      (node (ref "26") (pin "1") (pinfunction "1_1") (pintype "bidirectional"))
      (node (ref "D18") (pin "A") (pinfunction "A_A") (pintype "passive"))
    )
    (net (code "50") (name "Net-(27-Pad1)") (class "Default")
      (node (ref "27") (pin "1") (pinfunction "1_1") (pintype "bidirectional"))
      (node (ref "D19") (pin "A") (pinfunction "A_A") (pintype "passive"))
    )
    (net (code "51") (name "Net-(28-Pad1)") (class "Default")
      (node (ref "28") (pin "1") (pinfunction "1_1") (pintype "bidirectional"))
      (node (ref "D20") (pin "A") (pinfunction "A_A") (pintype "passive"))
    )
    (net (code "52") (name "Net-(29-Pad1)") (class "Default")
      (node (ref "29") (pin "1") (pinfunction "1_1") (pintype "bidirectional"))
      (node (ref "D21") (pin "A") (pinfunction "A_A") (pintype "passive"))
    )
    (net (code "53") (name "Net-(31-Pad1)") (class "Default")
      (node (ref "31") (pin "1") (pinfunction "1_1") (pintype "bidirectional"))
      (node (ref "D25") (pin "A") (pinfunction "A_A") (pintype "passive"))
    )
    (net (code "54") (name "Net-(32-Pad1)") (class "Default")
      (node (ref "32") (pin "1") (pinfunction "1_1") (pintype "bidirectional"))
      (node (ref "D26") (pin "A") (pinfunction "A_A") (pintype "passive"))
    )
    (net (code "55") (name "Net-(33-Pad1)") (class "Default")
      (node (ref "33") (pin "1") (pinfunction "1_1") (pintype "bidirectional"))
      (node (ref "D27") (pin "A") (pinfunction "A_A") (pintype "passive"))
    )
    (net (code "56") (name "Net-(34-Pad1)") (class "Default")
      (node (ref "34") (pin "1") (pinfunction "1_1") (pintype "bidirectional"))
      (node (ref "D28") (pin "A") (pinfunction "A_A") (pintype "passive"))
    )
    (net (code "57") (name "Net-(35-Pad1)") (class "Default")
      (node (ref "35") (pin "1") (pinfunction "1_1") (pintype "bidirectional"))
      (node (ref "D29") (pin "A") (pinfunction "A_A") (pintype "passive"))
    )
    (net (code "58") (name "Net-(36-Pad1)") (class "Default")
      (node (ref "36") (pin "1") (pinfunction "1_1") (pintype "bidirectional"))
      (node (ref "D30") (pin "A") (pinfunction "A_A") (pintype "passive"))
    )
    (net (code "59") (name "Net-(37-Pad1)") (class "Default")
      (node (ref "37") (pin "1") (pinfunction "1_1") (pintype "bidirectional"))
      (node (ref "D31") (pin "A") (pinfunction "A_A") (pintype "passive"))
    )
    (net (code "60") (name "Net-(38-Pad1)") (class "Default")
      (node (ref "38") (pin "1") (pinfunction "1_1") (pintype "bidirectional"))
      (node (ref "D32") (pin "A") (pinfunction "A_A") (pintype "passive"))
    )
    (net (code "61") (name "Net-(39-Pad1)") (class "Default")
      (node (ref "39") (pin "1") (pinfunction "1_1") (pintype "bidirectional"))
      (node (ref "D33") (pin "A") (pinfunction "A_A") (pintype "passive"))
    )
    (net (code "62") (name "Net-(41-Pad1)") (class "Default")
      (node (ref "41") (pin "1") (pinfunction "1_1") (pintype "bidirectional"))
      (node (ref "41ENC\\") (pin "S1") (pinfunction "S1_S1") (pintype "bidirectional"))
      (node (ref "D37") (pin "A") (pinfunction "A_A") (pintype "passive"))
    )
    (net (code "63") (name "Net-(42-Pad1)") (class "Default")
      (node (ref "42") (pin "1") (pinfunction "1_1") (pintype "bidirectional"))
      (node (ref "D38") (pin "A") (pinfunction "A_A") (pintype "passive"))
    )
    (net (code "64") (name "Net-(43-Pad1)") (class "Default")
      (node (ref "43") (pin "1") (pinfunction "1_1") (pintype "bidirectional"))
      (node (ref "D39") (pin "A") (pinfunction "A_A") (pintype "passive"))
    )
    (net (code "65") (name "Net-(44-Pad1)") (class "Default")
      (node (ref "44") (pin "1") (pinfunction "1_1") (pintype "bidirectional"))
      (node (ref "D40") (pin "A") (pinfunction "A_A") (pintype "passive"))
    )
    (net (code "66") (name "Net-(45-2-Pad1)") (class "Default")
      (node (ref "45") (pin "1") (pinfunction "1_1") (pintype "bidirectional"))
      (node (ref "45-2") (pin "1") (pinfunction "1_1") (pintype "bidirectional"))
      (node (ref "D41") (pin "A") (pinfunction "A_A") (pintype "passive"))
    )
    (net (code "67") (name "Net-(46-2-Pad1)") (class "Default")
      (node (ref "46") (pin "1") (pinfunction "1_1") (pintype "bidirectional"))
      (node (ref "46-2") (pin "1") (pinfunction "1_1") (pintype "bidirectional"))
      (node (ref "D42") (pin "A") (pinfunction "A_A") (pintype "passive"))
    )
    (net (code "68") (name "Net-(47-Pad1)") (class "Default")
      (node (ref "47") (pin "1") (pinfunction "1_1") (pintype "bidirectional"))
      (node (ref "D48") (pin "A") (pinfunction "A_A") (pintype "passive"))
    )
    (net (code "69") (name "Net-(48-2-Pad1)") (class "Default")
      (node (ref "48") (pin "1") (pinfunction "1_1") (pintype "bidirectional"))
      (node (ref "48-2") (pin "1") (pinfunction "1_1") (pintype "bidirectional"))
      (node (ref "D43") (pin "A") (pinfunction "A_A") (pintype "passive"))
    )
    (net (code "70") (name "Net-(49-Pad1)") (class "Default")
      (node (ref "49") (pin "1") (pinfunction "1_1") (pintype "bidirectional"))
      (node (ref "D44") (pin "A") (pinfunction "A_A") (pintype "passive"))
    )
    (net (code "71") (name "Net-(110-Pad1)") (class "Default")
      (node (ref "110") (pin "1") (pinfunction "1_1") (pintype "bidirectional"))
      (node (ref "D10") (pin "A") (pinfunction "A_A") (pintype "passive"))
    )
    (net (code "72") (name "Net-(111-Pad1)") (class "Default")
      (node (ref "111") (pin "1") (pinfunction "1_1") (pintype "bidirectional"))
      (node (ref "D11") (pin "A") (pinfunction "A_A") (pintype "passive"))
    )
    (net (code "73") (name "Net-(112-Pad1)") (class "Default")
      (node (ref "112") (pin "1") (pinfunction "1_1") (pintype "bidirectional"))
      (node (ref "D12") (pin "A") (pinfunction "A_A") (pintype "passive"))
    )
    (net (code "74") (name "Net-(210-Pad1)") (class "Default")
      (node (ref "210") (pin "1") (pinfunction "1_1") (pintype "bidirectional"))
      (node (ref "D22") (pin "A") (pinfunction "A_A") (pintype "passive"))
    )
    (net (code "75") (name "Net-(211-Pad1)") (class "Default")
      (node (ref "211") (pin "1") (pinfunction "1_1") (pintype "bidirectional"))
      (node (ref "D23") (pin "A") (pinfunction "A_A") (pintype "passive"))
    )
    (net (code "76") (name "Net-(212-Pad1)") (class "Default")
      (node (ref "212") (pin "1") (pinfunction "1_1") (pintype "bidirectional"))
      (node (ref "D24") (pin "A") (pinfunction "A_A") (pintype "passive"))
    )
    (net (code "77") (name "Net-(310-Pad1)") (class "Default")
      (node (ref "310") (pin "1") (pinfunction "1_1") (pintype "bidirectional"))
      (node (ref "D34") (pin "A") (pinfunction "A_A") (pintype "passive"))
    )
    (net (code "78") (name "Net-(311-Pad1)") (class "Default")
      (node (ref "311") (pin "1") (pinfunction "1_1") (pintype "bidirectional"))
      (node (ref "D35") (pin "A") (pinfunction "A_A") (pintype "passive"))
    )
    (net (code "79") (name "Net-(312-Pad1)") (class "Default")
      (node (ref "312") (pin "1") (pinfunction "1_1") (pintype "bidirectional"))
      (node (ref "D36") (pin "A") (pinfunction "A_A") (pintype "passive"))
    )
    (net (code "80") (name "Net-(410-Pad1)") (class "Default")
      (node (ref "410") (pin "1") (pinfunction "1_1") (pintype "bidirectional"))
      (node (ref "D45") (pin "A") (pinfunction "A_A") (pintype "passive"))
    )
    (net (code "81") (name "Net-(411-Pad1)") (class "Default")
      (node (ref "411") (pin "1") (pinfunction "1_1") (pintype "bidirectional"))
      (node (ref "D46") (pin "A") (pinfunction "A_A") (pintype "passive"))
    )
    (net (code "82") (name "Net-(412-Pad1)") (class "Default")
      (node (ref "412") (pin "1") (pinfunction "1_1") (pintype "bidirectional"))
      (node (ref "412ENC") (pin "S1") (pinfunction "S1_S1") (pintype "bidirectional"))
      (node (ref "D47") (pin "A") (pinfunction "A_A") (pintype "passive"))
    )
    (net (code "83") (name "Net-(D77-DO)") (class "Default")
      (node (ref "D77") (pin "2") (pinfunction "DO_2") (pintype "bidirectional"))
      (node (ref "D78") (pin "4") (pinfunction "DI_4") (pintype "bidirectional"))
    )
    (net (code "84") (name "Net-(D78-DO)") (class "Default")
      (node (ref "D78") (pin "2") (pinfunction "DO_2") (pintype "bidirectional"))
      (node (ref "D79") (pin "4") (pinfunction "DI_4") (pintype "bidirectional"))
    )
    (net (code "85") (name "Net-(D79-DO)") (class "Default")
      (node (ref "D79") (pin "2") (pinfunction "DO_2") (pintype "bidirectional"))
      (node (ref "D80") (pin "4") (pinfunction "DI_4") (pintype "bidirectional"))
    )
    (net (code "86") (name "Net-(D80-DO)") (class "Default")
      (node (ref "D80") (pin "2") (pinfunction "DO_2") (pintype "bidirectional"))
      (node (ref "D81") (pin "4") (pinfunction "DI_4") (pintype "bidirectional"))
    )
    (net (code "87") (name "Net-(D81-DO)") (class "Default")
      (node (ref "D81") (pin "2") (pinfunction "DO_2") (pintype "bidirectional"))
      (node (ref "D82") (pin "4") (pinfunction "DI_4") (pintype "bidirectional"))
    )
    (net (code "88") (name "Net-(D82-DO)") (class "Default")
      (node (ref "D82") (pin "2") (pinfunction "DO_2") (pintype "bidirectional"))
      (node (ref "D83") (pin "4") (pinfunction "DI_4") (pintype "bidirectional"))
    )
    (net (code "89") (name "Net-(D83-DO)") (class "Default")
      (node (ref "D83") (pin "2") (pinfunction "DO_2") (pintype "bidirectional"))
      (node (ref "D84") (pin "4") (pinfunction "DI_4") (pintype "bidirectional"))
    )
    (net (code "90") (name "Net-(D84-DO)") (class "Default")
      (node (ref "D84") (pin "2") (pinfunction "DO_2") (pintype "bidirectional"))
      (node (ref "D85") (pin "4") (pinfunction "DI_4") (pintype "bidirectional"))
    )
    (net (code "91") (name "Net-(D85-DO)") (class "Default")
      (node (ref "D85") (pin "2") (pinfunction "DO_2") (pintype "bidirectional"))
      (node (ref "D86") (pin "4") (pinfunction "DI_4") (pintype "bidirectional"))
    )
    (net (code "92") (name "Net-(D86-DO)") (class "Default")
      (node (ref "D86") (pin "2") (pinfunction "DO_2") (pintype "bidirectional"))
      (node (ref "D87") (pin "4") (pinfunction "DI_4") (pintype "bidirectional"))
    )
    (net (code "93") (name "Net-(D87-DO)") (class "Default")
      (node (ref "D87") (pin "2") (pinfunction "DO_2") (pintype "bidirectional"))
      (node (ref "D88") (pin "4") (pinfunction "DI_4") (pintype "bidirectional"))
    )
    (net (code "94") (name "Net-(FUSE-Pad1)") (class "Default")
      (node (ref "FUSE") (pin "1") (pinfunction "1_1") (pintype "passive"))
      (node (ref "J3") (pin "VBUS") (pinfunction "VBUS_VBUS") (pintype "bidirectional"))
      (node (ref "J3") (pin "VBUS2") (pinfunction "VBUS_VBUS2") (pintype "bidirectional"))
    )
    (net (code "95") (name "Net-(IC1-VDD)") (class "Default")
      (node (ref "C5") (pin "1") (pinfunction "1_1") (pintype "passive"))
      (node (ref "IC1") (pin "2") (pinfunction "VDD_2") (pintype "bidirectional"))
      (node (ref "R15") (pin "1") (pinfunction "1_1") (pintype "passive"))
    )
    (net (code "96") (name "Net-(IC2-PROG)") (class "Default")
      (node (ref "IC2") (pin "5") (pinfunction "PROG_5") (pintype "bidirectional"))
      (node (ref "R13") (pin "2") (pinfunction "2_2") (pintype "passive"))
    )
    (net (code "97") (name "Net-(IC2-~{CHRG})") (class "Default")
      (node (ref "IC2") (pin "1") (pinfunction "~{CHRG}_1") (pintype "bidirectional"))
      (node (ref "R14") (pin "2") (pinfunction "2_2") (pintype "passive"))
    )
    (net (code "98") (name "Net-(J1-COM)") (class "Default")
      (node (ref "J1") (pin "2") (pinfunction "COM_2") (pintype "bidirectional"))
      (node (ref "Q2") (pin "1") (pinfunction "G_1") (pintype "passive"))
      (node (ref "R4") (pin "2") (pinfunction "2_2") (pintype "passive"))
    )
    (net (code "99") (name "Net-(J3-CC1)") (class "Default")
      (node (ref "J3") (pin "A5") (pinfunction "CC1_A5") (pintype "bidirectional"))
      (node (ref "R12") (pin "2") (pinfunction "2_2") (pintype "passive"))
    )
    (net (code "100") (name "Net-(J3-CC2)") (class "Default")
      (node (ref "J3") (pin "B5") (pinfunction "CC2_B5") (pintype "bidirectional"))
      (node (ref "R11") (pin "2") (pinfunction "2_2") (pintype "passive"))
    )
    (net (code "101") (name "Net-(LED1-PadC)") (class "Default")
      (node (ref "LED1") (pin "C") (pinfunction "C_C") (pintype "passive"))
      (node (ref "R1") (pin "2") (pinfunction "2_2") (pintype "passive"))
    )
    (net (code "102") (name "Net-(LED2-PadC)") (class "Default")
      (node (ref "LED2") (pin "C") (pinfunction "C_C") (pintype "passive"))
      (node (ref "R14") (pin "1") (pinfunction "1_1") (pintype "passive"))
    )
    (net (code "103") (name "Net-(Q2-D)") (class "Default")
      (node (ref "Q2") (pin "3") (pinfunction "D_3") (pintype "passive"))
      (node (ref "Q5") (pin "3") (pinfunction "D_3") (pintype "passive"))
    )
    (net (code "104") (name "Net-(Q3-G)") (class "Default")
      (node (ref "Q3") (pin "1") (pinfunction "G_1") (pintype "passive"))
      (node (ref "Q6") (pin "3") (pinfunction "D_3") (pintype "passive"))
      (node (ref "R5") (pin "2") (pinfunction "2_2") (pintype "passive"))
    )
    (net (code "105") (name "Net-(U1A-OUT_ANT)") (class "Default")
      (node (ref "U1") (pin "20") (pinfunction "OUT_ANT_20") (pintype "bidirectional"))
      (node (ref "U1") (pin "22") (pinfunction "OUT_MOD_22") (pintype "bidirectional"))
    )
    (net (code "106") (name "V_BATT") (class "Default")
      (node (ref "IC2") (pin "3") (pinfunction "BAT_3") (pintype "bidirectional"))
      (node (ref "J1") (pin "1") (pinfunction "NO_1") (pintype "bidirectional"))
      (node (ref "J4") (pin "1") (pinfunction "1_1") (pintype "passive"))
      (node (ref "Q2") (pin "2") (pinfunction "S_2") (pintype "passive"))
      (node (ref "R15") (pin "2") (pinfunction "2_2") (pintype "passive"))
      (node (ref "R19") (pin "1") (pinfunction "1_1") (pintype "passive"))
      (node (ref "X1") (pin "2") (pinfunction "2_2") (pintype "passive"))
    )
    (net (code "107") (name "V_USB") (class "Default")
      (node (ref "C4") (pin "1") (pinfunction "1_1") (pintype "passive"))
      (node (ref "D63") (pin "2") (pinfunction "A_2") (pintype "bidirectional"))
      (node (ref "D67") (pin "A") (pinfunction "A_A") (pintype "passive"))
      (node (ref "FUSE") (pin "2") (pinfunction "2_2") (pintype "passive"))
      (node (ref "IC2") (pin "4") (pinfunction "VCC_4") (pintype "bidirectional"))
      (node (ref "LED2") (pin "A") (pinfunction "A_A") (pintype "passive"))
      (node (ref "Q5") (pin "1") (pinfunction "G_1") (pintype "passive"))
      (node (ref "R17") (pin "2") (pinfunction "2_2") (pintype "passive"))
      (node (ref "U1") (pin "12") (pinfunction "VBUS_12") (pintype "power_in"))
    )
    (net (code "108") (name "unconnected-(D49-PadA)") (class "Default")
      (node (ref "D49") (pin "A") (pinfunction "A_A") (pintype "passive"))
    )
    (net (code "109") (name "unconnected-(D49-PadC)") (class "Default")
      (node (ref "D49") (pin "C") (pinfunction "C_C") (pintype "passive"))
    )
    (net (code "110") (name "unconnected-(D50-PadA)") (class "Default")
      (node (ref "D50") (pin "A") (pinfunction "A_A") (pintype "passive"))
    )
    (net (code "111") (name "unconnected-(D50-PadC)") (class "Default")
      (node (ref "D50") (pin "C") (pinfunction "C_C") (pintype "passive"))
    )
    (net (code "112") (name "unconnected-(D51-PadA)") (class "Default")
      (node (ref "D51") (pin "A") (pinfunction "A_A") (pintype "passive"))
    )
    (net (code "113") (name "unconnected-(D51-PadC)") (class "Default")
      (node (ref "D51") (pin "C") (pinfunction "C_C") (pintype "passive"))
    )
    (net (code "114") (name "unconnected-(D52-PadA)") (class "Default")
      (node (ref "D52") (pin "A") (pinfunction "A_A") (pintype "passive"))
    )
    (net (code "115") (name "unconnected-(D52-PadC)") (class "Default")
      (node (ref "D52") (pin "C") (pinfunction "C_C") (pintype "passive"))
    )
    (net (code "116") (name "unconnected-(J1-NC-Pad3)") (class "Default")
      (node (ref "J1") (pin "3") (pinfunction "NC_3") (pintype "no_connect"))
    )
    (net (code "117") (name "unconnected-(J2-SWO{slash}TDO-Pad6)") (class "Default")
      (node (ref "J2") (pin "6") (pinfunction "SWO/TDO_6") (pintype "bidirectional"))
    )
    (net (code "118") (name "unconnected-(U1A-P0.07-Pad33)") (class "Default")
      (node (ref "U1") (pin "33") (pinfunction "P0.07_33") (pintype "bidirectional"))
    )
    (net (code "119") (name "unconnected-(U1A-P0.14-Pad5)") (class "Default")
      (node (ref "U1") (pin "5") (pinfunction "P0.14_5") (pintype "bidirectional"))
    )
    (net (code "120") (name "unconnected-(U1A-P0.22-Pad17)") (class "Default")
      (node (ref "U1") (pin "17") (pinfunction "P0.22_17") (pintype "bidirectional"))
    )
    (net (code "121") (name "unconnected-(U1A-P0.25-Pad41)") (class "Default")
      (node (ref "U1") (pin "41") (pinfunction "P0.25_41") (pintype "bidirectional"))
    )
    (net (code "122") (name "unconnected-(U1A-P0.27-Pad39)") (class "Default")
      (node (ref "U1") (pin "39") (pinfunction "P0.27_39") (pintype "bidirectional"))
    )
    (net (code "123") (name "unconnected-(U1A-P1.00-Pad57)") (class "Default")
      (node (ref "U1") (pin "57") (pinfunction "P1.00_57") (pintype "bidirectional"))
    )
    (net (code "124") (name "unconnected-(U1A-P1.01-Pad64)") (class "Default")
      (node (ref "U1") (pin "64") (pinfunction "P1.01_64") (pintype "bidirectional"))
    )
    (net (code "125") (name "unconnected-(U1A-P1.02-Pad49)") (class "Default")
      (node (ref "U1") (pin "49") (pinfunction "P1.02_49") (pintype "bidirectional"))
    )
    (net (code "126") (name "unconnected-(U1A-P1.03-Pad58)") (class "Default")
      (node (ref "U1") (pin "58") (pinfunction "P1.03_58") (pintype "bidirectional"))
    )
    (net (code "127") (name "unconnected-(U1A-P1.04-Pad63)") (class "Default")
      (node (ref "U1") (pin "63") (pinfunction "P1.04_63") (pintype "bidirectional"))
    )
    (net (code "128") (name "unconnected-(U1A-P1.05-Pad54)") (class "Default")
      (node (ref "U1") (pin "54") (pinfunction "P1.05_54") (pintype "bidirectional"))
    )
    (net (code "129") (name "unconnected-(U1A-P1.06-Pad50)") (class "Default")
      (node (ref "U1") (pin "50") (pinfunction "P1.06_50") (pintype "bidirectional"))
    )
    (net (code "130") (name "unconnected-(U1A-P1.07-Pad62)") (class "Default")
      (node (ref "U1") (pin "62") (pinfunction "P1.07_62") (pintype "bidirectional"))
    )
    (net (code "131") (name "unconnected-(U1A-P1.10-Pad60)") (class "Default")
      (node (ref "U1") (pin "60") (pinfunction "P1.10_60") (pintype "bidirectional"))
    )
    (net (code "132") (name "unconnected-(U1A-P1.11-Pad61)") (class "Default")
      (node (ref "U1") (pin "61") (pinfunction "P1.11_61") (pintype "bidirectional"))
    )
    (net (code "133") (name "unconnected-(U1A-P1.12-Pad59)") (class "Default")
      (node (ref "U1") (pin "59") (pinfunction "P1.12_59") (pintype "bidirectional"))
    )
    (net (code "134") (name "unconnected-(U1A-P1.13-Pad53)") (class "Default")
      (node (ref "U1") (pin "53") (pinfunction "P1.13_53") (pintype "bidirectional"))
    )
    (net (code "135") (name "unconnected-(U1A-P1.14-Pad52)") (class "Default")
      (node (ref "U1") (pin "52") (pinfunction "P1.14_52") (pintype "bidirectional"))
    )
    (net (code "136") (name "unconnected-(U1A-P1.15-Pad51)") (class "Default")
      (node (ref "U1") (pin "51") (pinfunction "P1.15_51") (pintype "bidirectional"))
    )
    (net (code "137") (name "unconnected-(U1B-NC-Pad65)") (class "Default")
      (node (ref "U1") (pin "65") (pinfunction "NC_65") (pintype "passive"))
    )
    (net (code "138") (name "unconnected-(U1B-NC-Pad66)") (class "Default")
      (node (ref "U1") (pin "66") (pinfunction "NC_66") (pintype "passive"))
    )
    (net (code "139") (name "unconnected-(U1B-NC-Pad67)") (class "Default")
      (node (ref "U1") (pin "67") (pinfunction "NC_67") (pintype "passive"))
    )
    (net (code "140") (name "unconnected-(U1B-NC-Pad68)") (class "Default")
      (node (ref "U1") (pin "68") (pinfunction "NC_68") (pintype "passive"))
    )
    (net (code "141") (name "unconnected-(U1B-NC-Pad69)") (class "Default")
      (node (ref "U1") (pin "69") (pinfunction "NC_69") (pintype "passive"))
    )
    (net (code "142") (name "unconnected-(U1B-NC-Pad70)") (class "Default")
      (node (ref "U1") (pin "70") (pinfunction "NC_70") (pintype "passive"))
    )
    (net (code "143") (name "unconnected-(U1B-NC-Pad71)") (class "Default")
      (node (ref "U1") (pin "71") (pinfunction "NC_71") (pintype "passive"))
    )
    (net (code "144") (name "unconnected-(U1B-NC-Pad72)") (class "Default")
      (node (ref "U1") (pin "72") (pinfunction "NC_72") (pintype "passive"))
    )
    (net (code "145") (name "unconnected-(U1B-NC-Pad73)") (class "Default")
      (node (ref "U1") (pin "73") (pinfunction "NC_73") (pintype "passive"))
    )
    (net (code "146") (name "unconnected-(U1B-NC-Pad74)") (class "Default")
      (node (ref "U1") (pin "74") (pinfunction "NC_74") (pintype "passive"))
    )
    (net (code "147") (name "unconnected-(U1B-NC-Pad75)") (class "Default")
      (node (ref "U1") (pin "75") (pinfunction "NC_75") (pintype "passive"))
    )
    (net (code "148") (name "unconnected-(U1B-NC-Pad76)") (class "Default")
      (node (ref "U1") (pin "76") (pinfunction "NC_76") (pintype "passive"))
    )
    (net (code "149") (name "unconnected-(U1B-NC-Pad77)") (class "Default")
      (node (ref "U1") (pin "77") (pinfunction "NC_77") (pintype "passive"))
    )
    (net (code "150") (name "unconnected-(U1B-NC-Pad78)") (class "Default")
      (node (ref "U1") (pin "78") (pinfunction "NC_78") (pintype "passive"))
    )
  )
)
